# QuadFM.net
KiCad netlist of a schematic drawn in EAGLE
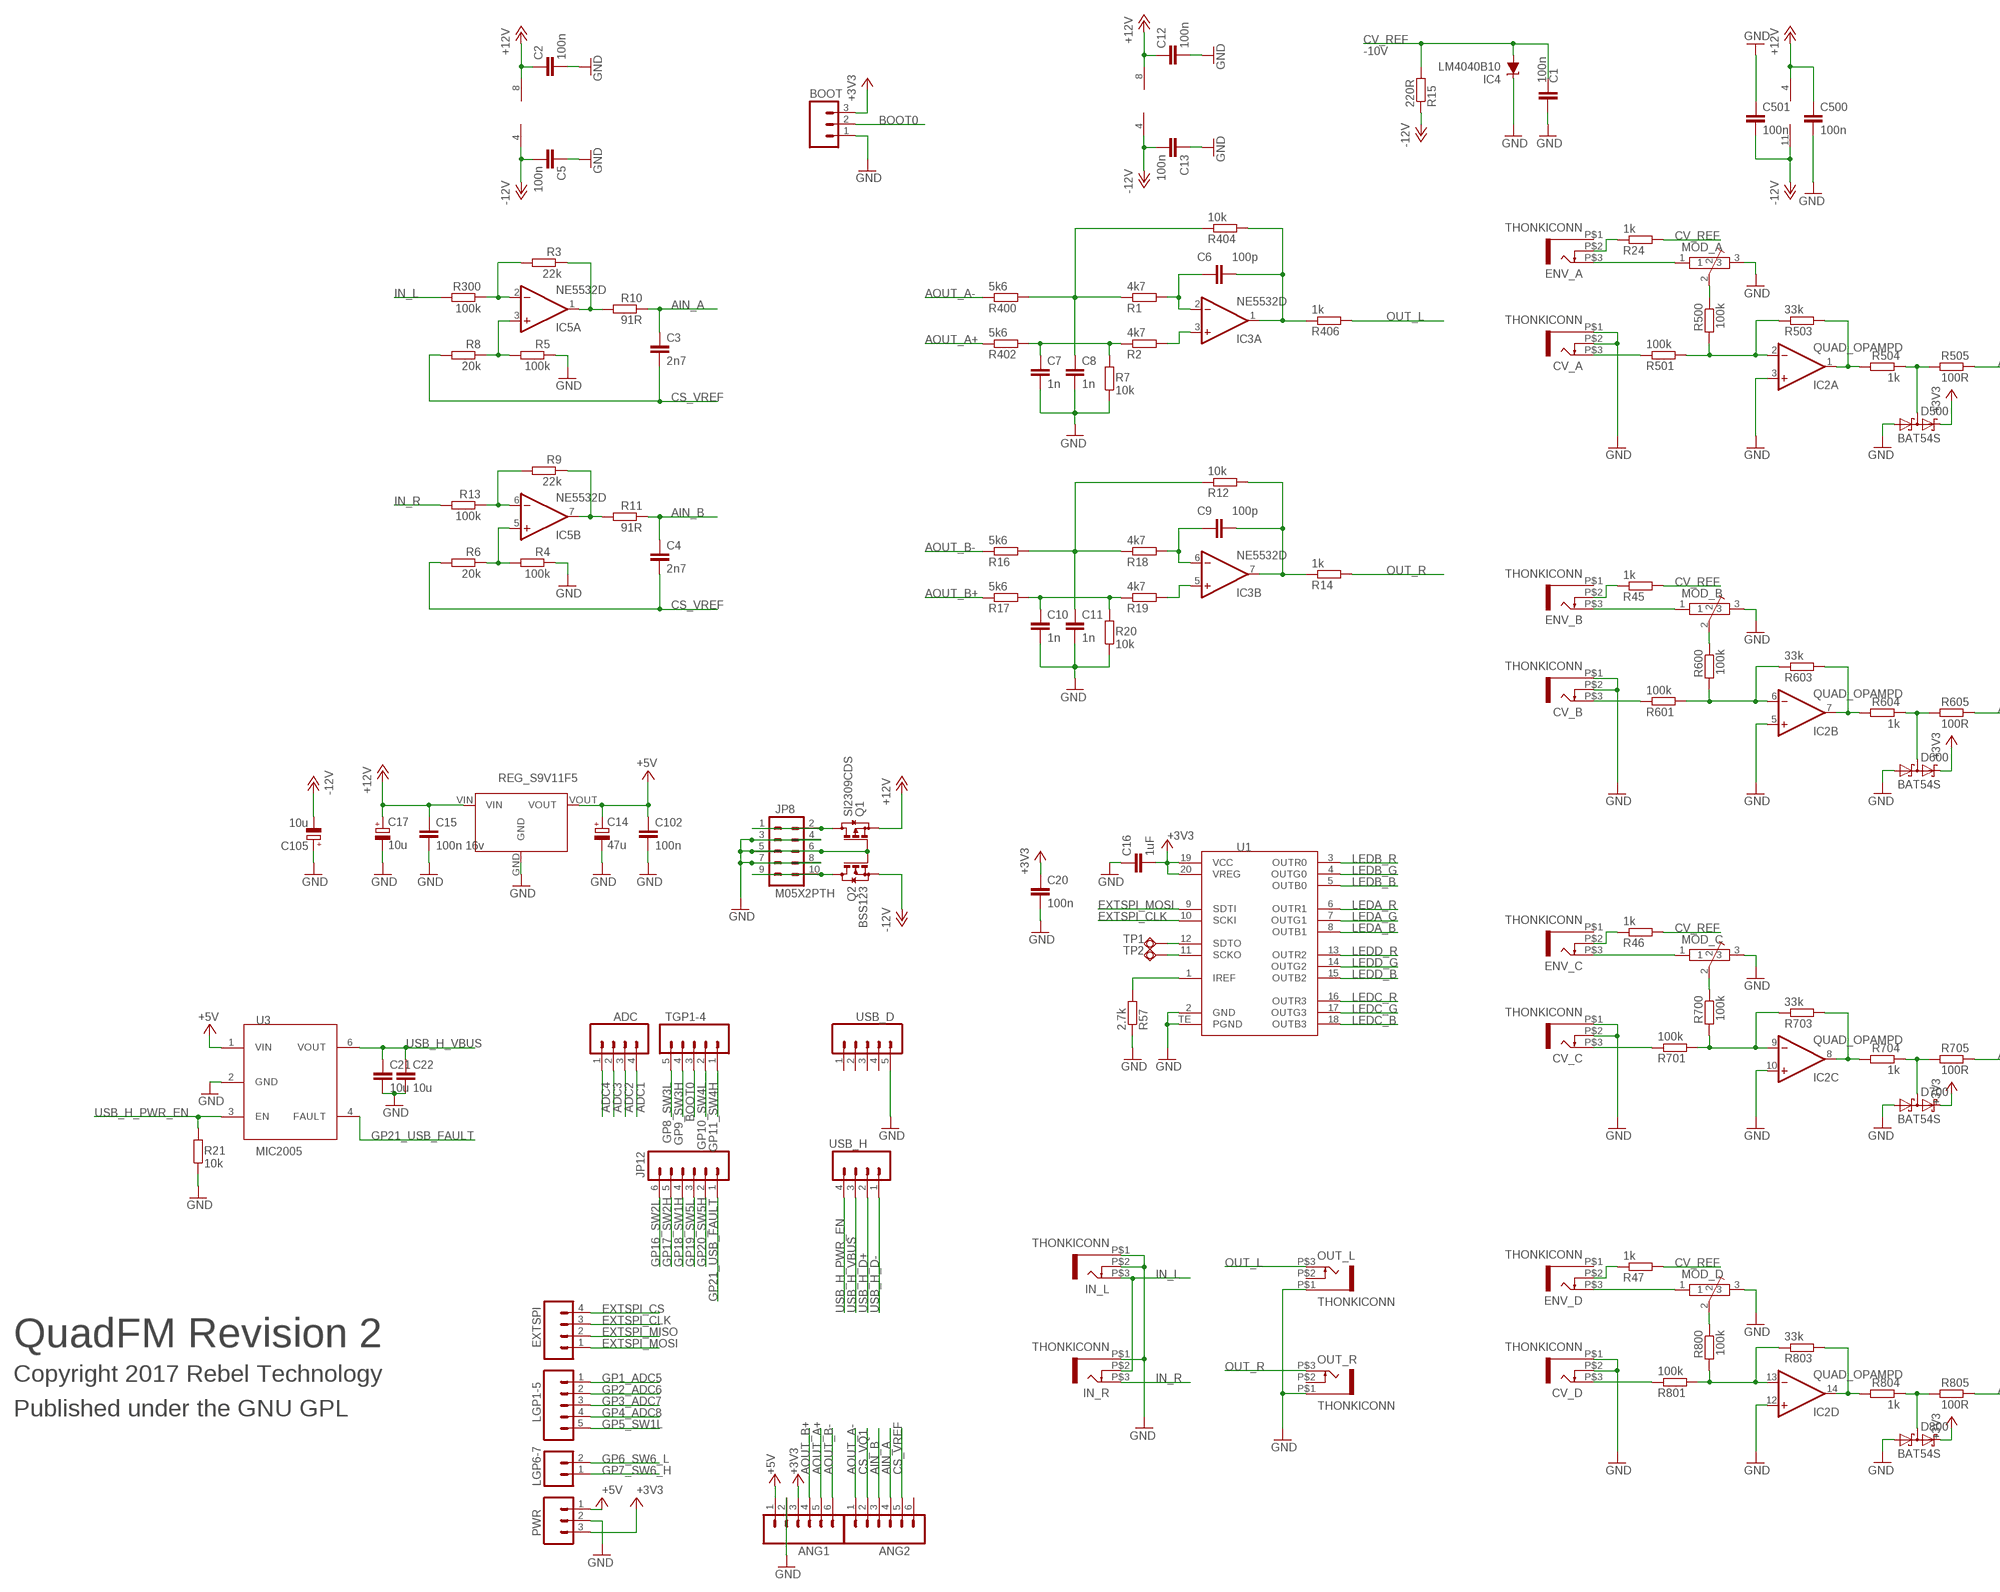
[diagram p0: schematic, sheet 1, part 1 of 2]
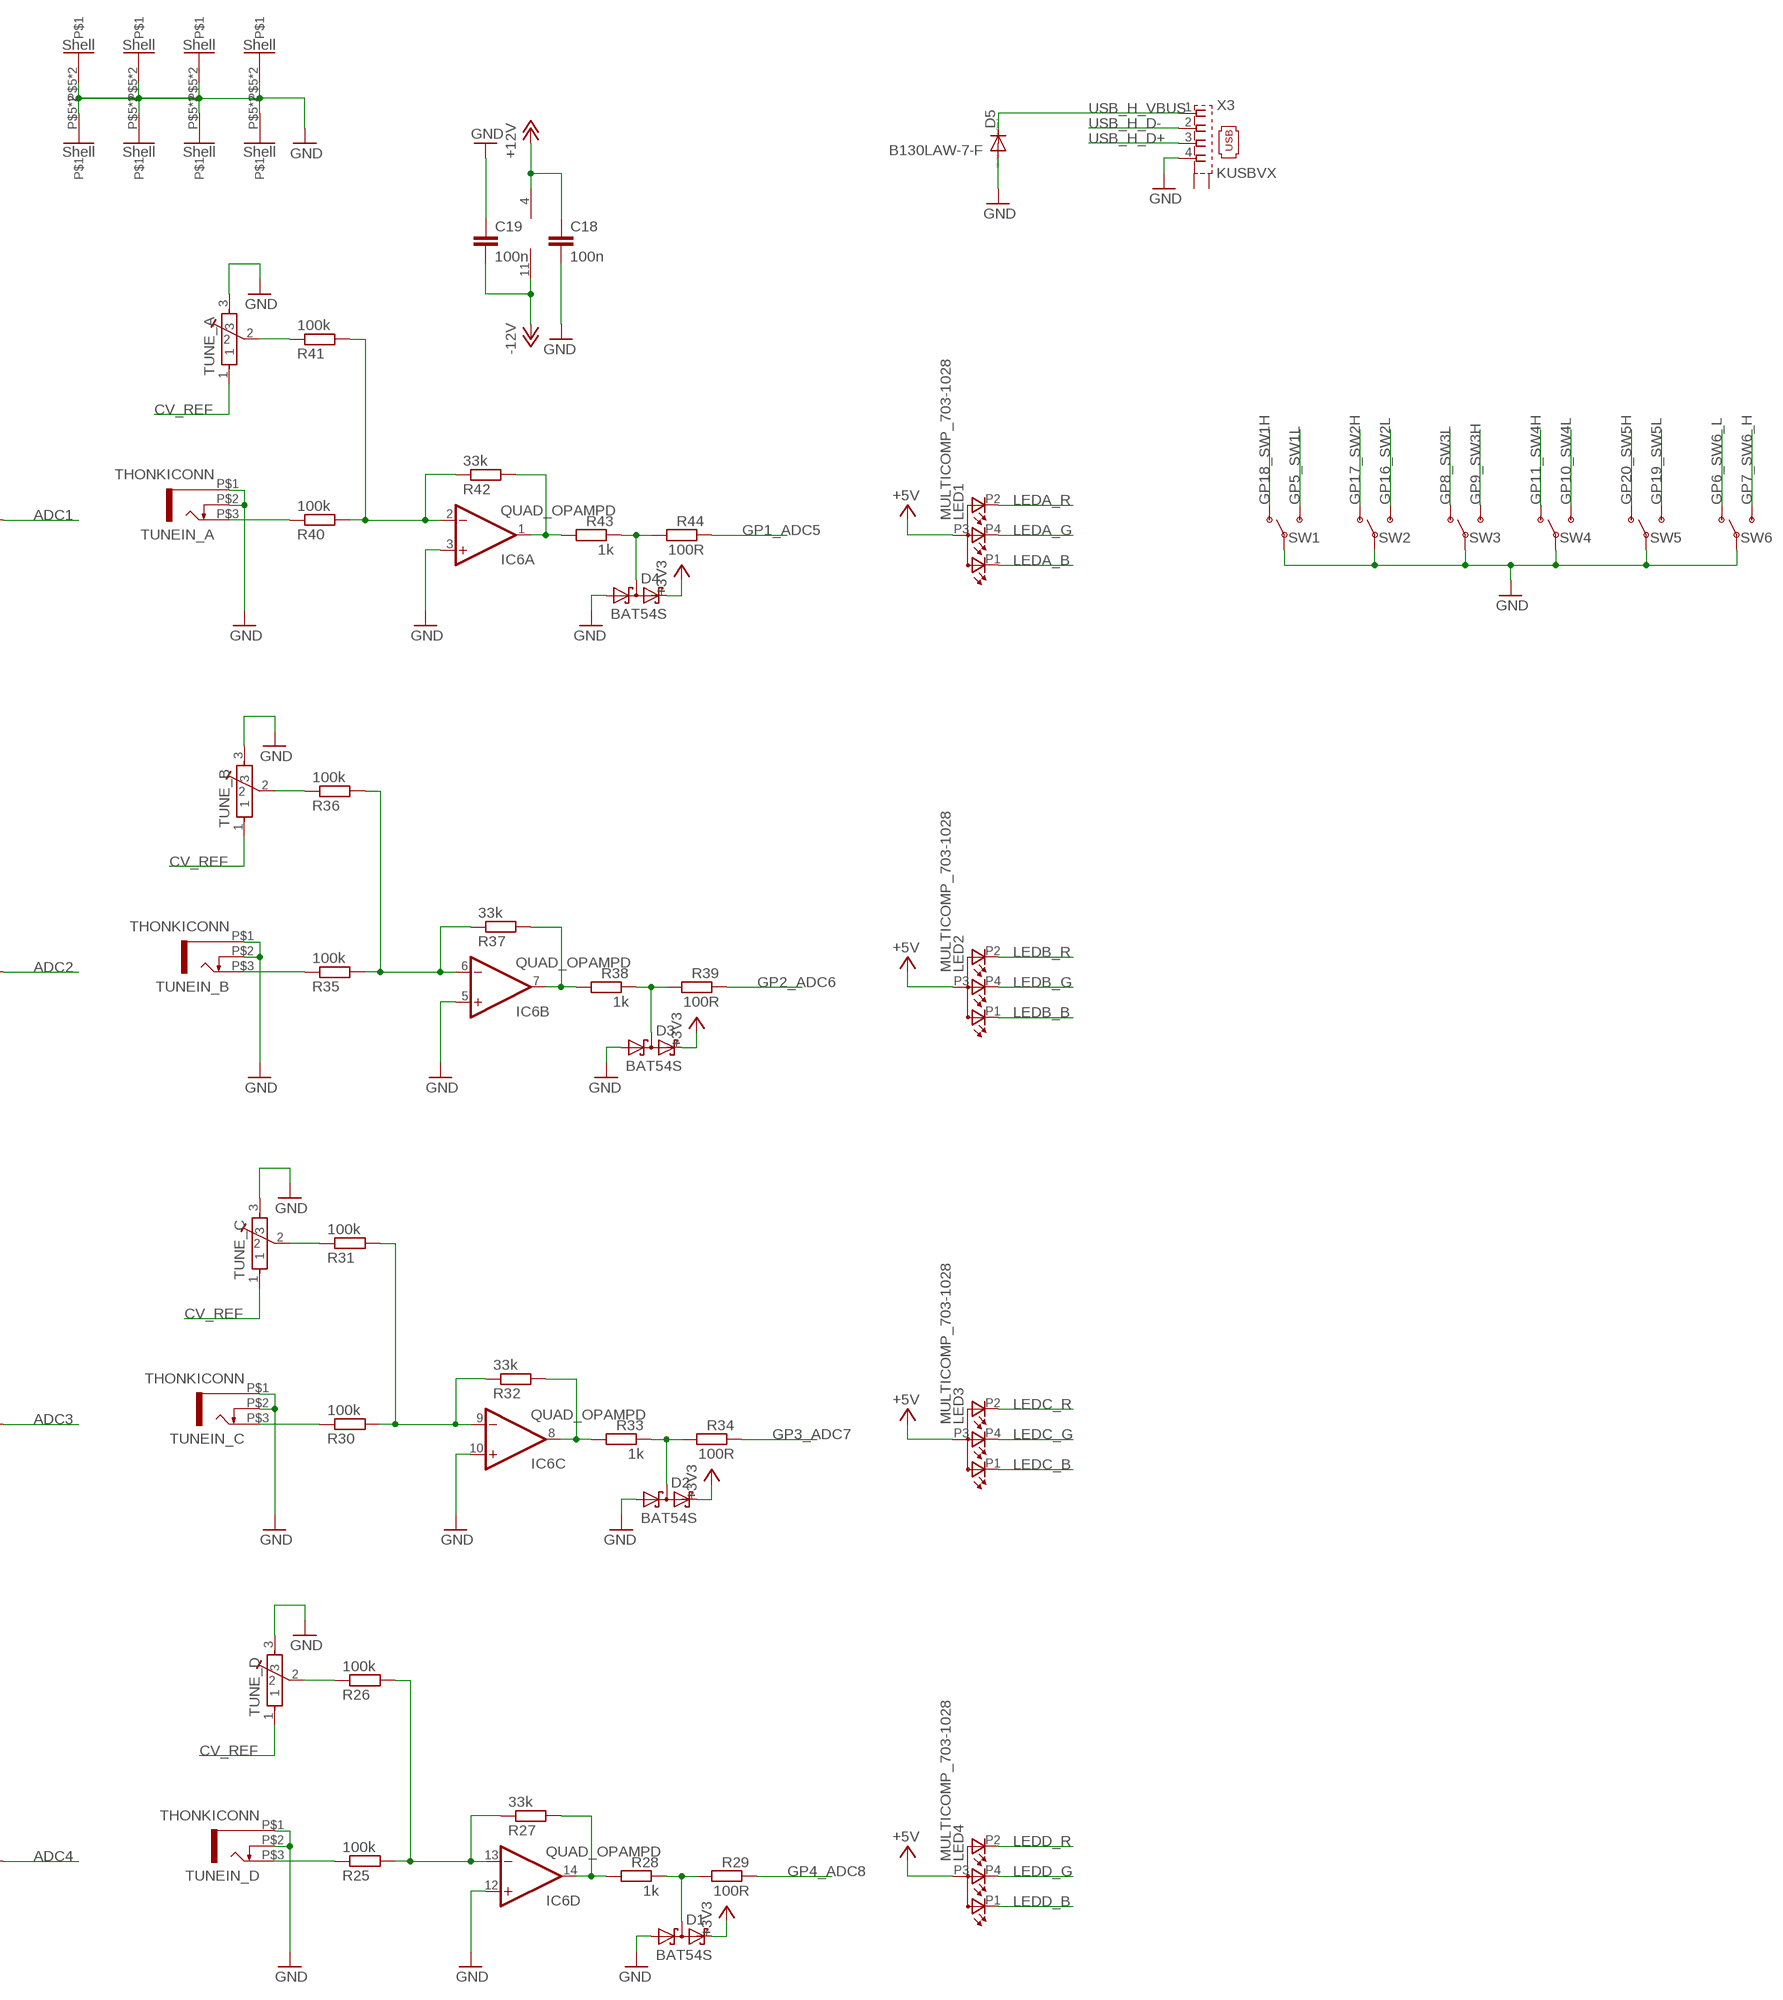
[diagram p1: schematic, sheet 1, part 2 of 2]

(export (version "E")
  (design (tool "Eeschema 10.0.6"))
  (components
    (comp (ref "ADC")
      (value "M04PTH")
      (footprint "eagle-import:1X04")
      (libsource (lib "eagle-import") (part "M04PTH"))
    )
    (comp (ref "ANG1")
      (value "M06SIP")
      (footprint "eagle-import:1X06")
      (libsource (lib "eagle-import") (part "M06SIP"))
    )
    (comp (ref "ANG2")
      (value "M06SIP")
      (footprint "eagle-import:1X06")
      (libsource (lib "eagle-import") (part "M06SIP"))
    )
    (comp (ref "BOOT")
      (value "M03PTH")
      (footprint "eagle-import:1X03")
      (libsource (lib "eagle-import") (part "M03PTH"))
    )
    (comp (ref "C1")
      (value "100n")
      (footprint "eagle-import:C0603")
      (libsource (lib "eagle-import") (part "resistor_C-EUC0603"))
    )
    (comp (ref "C2")
      (value "100n")
      (footprint "eagle-import:C0603")
      (libsource (lib "eagle-import") (part "resistor_C-EUC0603"))
    )
    (comp (ref "C3")
      (value "2n7")
      (footprint "eagle-import:C0603")
      (libsource (lib "eagle-import") (part "resistor_C-EUC0603"))
    )
    (comp (ref "C4")
      (value "2n7")
      (footprint "eagle-import:C0603")
      (libsource (lib "eagle-import") (part "resistor_C-EUC0603"))
    )
    (comp (ref "C5")
      (value "100n")
      (footprint "eagle-import:C0603")
      (libsource (lib "eagle-import") (part "resistor_C-EUC0603"))
    )
    (comp (ref "C6")
      (value "100p")
      (footprint "eagle-import:C0603")
      (libsource (lib "eagle-import") (part "resistor_C-EUC0603"))
    )
    (comp (ref "C7")
      (value "1n")
      (footprint "eagle-import:C0603")
      (libsource (lib "eagle-import") (part "resistor_C-EUC0603"))
    )
    (comp (ref "C8")
      (value "1n")
      (footprint "eagle-import:C0603")
      (libsource (lib "eagle-import") (part "resistor_C-EUC0603"))
    )
    (comp (ref "C9")
      (value "100p")
      (footprint "eagle-import:C0603")
      (libsource (lib "eagle-import") (part "resistor_C-EUC0603"))
    )
    (comp (ref "C10")
      (value "1n")
      (footprint "eagle-import:C0603")
      (libsource (lib "eagle-import") (part "resistor_C-EUC0603"))
    )
    (comp (ref "C11")
      (value "1n")
      (footprint "eagle-import:C0603")
      (libsource (lib "eagle-import") (part "resistor_C-EUC0603"))
    )
    (comp (ref "C12")
      (value "100n")
      (footprint "eagle-import:C0603")
      (libsource (lib "eagle-import") (part "resistor_C-EUC0603"))
    )
    (comp (ref "C13")
      (value "100n")
      (footprint "eagle-import:C0603")
      (libsource (lib "eagle-import") (part "resistor_C-EUC0603"))
    )
    (comp (ref "C14")
      (value "47u")
      (footprint "eagle-import:CPOL-5")
      (libsource (lib "eagle-import") (part "CPOL-EU153CLV-0505"))
    )
    (comp (ref "C15")
      (value "100n 16v")
      (footprint "eagle-import:C0603")
      (libsource (lib "eagle-import") (part "C-EUC0603"))
    )
    (comp (ref "C16")
      (value "1uF")
      (footprint "eagle-import:C0603")
      (libsource (lib "eagle-import") (part "C-EUC0603"))
    )
    (comp (ref "C17")
      (value "10u")
      (footprint "eagle-import:153CLV-0405")
      (libsource (lib "eagle-import") (part "CPOL-EU153CLV-0405"))
    )
    (comp (ref "C18")
      (value "100n")
      (footprint "eagle-import:C0603")
      (libsource (lib "eagle-import") (part "resistor_C-EUC0603"))
    )
    (comp (ref "C19")
      (value "100n")
      (footprint "eagle-import:C0603")
      (libsource (lib "eagle-import") (part "resistor_C-EUC0603"))
    )
    (comp (ref "C20")
      (value "100n")
      (footprint "eagle-import:C0603")
      (libsource (lib "eagle-import") (part "resistor_C-EUC0603"))
    )
    (comp (ref "C21")
      (value "10u")
      (footprint "eagle-import:C0603")
      (libsource (lib "eagle-import") (part "resistor_C-EUC0603"))
    )
    (comp (ref "C22")
      (value "10u")
      (footprint "eagle-import:C0603")
      (libsource (lib "eagle-import") (part "resistor_C-EUC0603"))
    )
    (comp (ref "C102")
      (value "100n")
      (footprint "eagle-import:C0603")
      (libsource (lib "eagle-import") (part "C-EUC0603"))
    )
    (comp (ref "C105")
      (value "10u")
      (footprint "eagle-import:153CLV-0405")
      (libsource (lib "eagle-import") (part "CPOL-EU153CLV-0405"))
    )
    (comp (ref "C500")
      (value "100n")
      (footprint "eagle-import:C0603")
      (libsource (lib "eagle-import") (part "resistor_C-EUC0603"))
    )
    (comp (ref "C501")
      (value "100n")
      (footprint "eagle-import:C0603")
      (libsource (lib "eagle-import") (part "resistor_C-EUC0603"))
    )
    (comp (ref "CV_A")
      (value "THONKICONN")
      (footprint "eagle-import:THONKICONN")
      (libsource (lib "eagle-import") (part "THONKICONN"))
    )
    (comp (ref "CV_B")
      (value "THONKICONN")
      (footprint "eagle-import:THONKICONN")
      (libsource (lib "eagle-import") (part "THONKICONN"))
    )
    (comp (ref "CV_C")
      (value "THONKICONN")
      (footprint "eagle-import:THONKICONN")
      (libsource (lib "eagle-import") (part "THONKICONN"))
    )
    (comp (ref "CV_D")
      (value "THONKICONN")
      (footprint "eagle-import:THONKICONN")
      (libsource (lib "eagle-import") (part "THONKICONN"))
    )
    (comp (ref "D1")
      (value "BAT54S")
      (footprint "eagle-import:SOT23")
      (libsource (lib "eagle-import") (part "BAT54S"))
    )
    (comp (ref "D2")
      (value "BAT54S")
      (footprint "eagle-import:SOT23")
      (libsource (lib "eagle-import") (part "BAT54S"))
    )
    (comp (ref "D3")
      (value "BAT54S")
      (footprint "eagle-import:SOT23")
      (libsource (lib "eagle-import") (part "BAT54S"))
    )
    (comp (ref "D4")
      (value "BAT54S")
      (footprint "eagle-import:SOT23")
      (libsource (lib "eagle-import") (part "BAT54S"))
    )
    (comp (ref "D5")
      (value "B130LAW-7-F")
      (footprint "eagle-import:SOD123")
      (libsource (lib "eagle-import") (part "DIODE-SOD123"))
    )
    (comp (ref "D500")
      (value "BAT54S")
      (footprint "eagle-import:SOT23")
      (libsource (lib "eagle-import") (part "BAT54S"))
    )
    (comp (ref "D600")
      (value "BAT54S")
      (footprint "eagle-import:SOT23")
      (libsource (lib "eagle-import") (part "BAT54S"))
    )
    (comp (ref "D700")
      (value "BAT54S")
      (footprint "eagle-import:SOT23")
      (libsource (lib "eagle-import") (part "BAT54S"))
    )
    (comp (ref "D800")
      (value "BAT54S")
      (footprint "eagle-import:SOT23")
      (libsource (lib "eagle-import") (part "BAT54S"))
    )
    (comp (ref "ENV_A")
      (value "THONKICONN")
      (footprint "eagle-import:THONKICONN")
      (libsource (lib "eagle-import") (part "THONKICONN"))
    )
    (comp (ref "ENV_B")
      (value "THONKICONN")
      (footprint "eagle-import:THONKICONN")
      (libsource (lib "eagle-import") (part "THONKICONN"))
    )
    (comp (ref "ENV_C")
      (value "THONKICONN")
      (footprint "eagle-import:THONKICONN")
      (libsource (lib "eagle-import") (part "THONKICONN"))
    )
    (comp (ref "ENV_D")
      (value "THONKICONN")
      (footprint "eagle-import:THONKICONN")
      (libsource (lib "eagle-import") (part "THONKICONN"))
    )
    (comp (ref "EXTSPI")
      (value "M04PTH")
      (footprint "eagle-import:1X04")
      (libsource (lib "eagle-import") (part "M04PTH"))
    )
    (comp (ref "IC2")
      (value "QUAD_OPAMPD")
      (footprint "eagle-import:SO14")
      (libsource (lib "eagle-import") (part "QUAD_OPAMPD"))
    )
    (comp (ref "IC3")
      (value "NE5532D")
      (footprint "eagle-import:SO08")
      (libsource (lib "eagle-import") (part "NE5532D"))
    )
    (comp (ref "IC4")
      (value "LM4040B10")
      (footprint "eagle-import:DBZ_R-PDSO-G3")
      (fields (field (name "MF") "TEXAS INSTRUMENT CONNECTORS") (field (name "MPN") "LM4041C12QDBZT"))
      (libsource (lib "eagle-import") (part "LM4041DBZC12"))
    )
    (comp (ref "IC5")
      (value "NE5532D")
      (footprint "eagle-import:SO08")
      (libsource (lib "eagle-import") (part "NE5532D"))
    )
    (comp (ref "IC6")
      (value "QUAD_OPAMPD")
      (footprint "eagle-import:SO14")
      (libsource (lib "eagle-import") (part "QUAD_OPAMPD"))
    )
    (comp (ref "IN_L")
      (value "THONKICONN")
      (footprint "eagle-import:THONKICONN")
      (libsource (lib "eagle-import") (part "THONKICONN"))
    )
    (comp (ref "IN_R")
      (value "THONKICONN")
      (footprint "eagle-import:THONKICONN")
      (libsource (lib "eagle-import") (part "THONKICONN"))
    )
    (comp (ref "JP8")
      (value "M05X2PTH")
      (footprint "eagle-import:AVR_ICSP")
      (libsource (lib "eagle-import") (part "M05X2PTH"))
    )
    (comp (ref "JP12")
      (value "M06SIP")
      (footprint "eagle-import:1X06")
      (libsource (lib "eagle-import") (part "M06SIP"))
    )
    (comp (ref "LED1")
      (value "MULTICOMP_703-1028")
      (footprint "eagle-import:RGB-LED-703-1028")
      (libsource (lib "eagle-import") (part "MULTICOMP_703-1028"))
    )
    (comp (ref "LED2")
      (value "MULTICOMP_703-1028")
      (footprint "eagle-import:RGB-LED-703-1028")
      (libsource (lib "eagle-import") (part "MULTICOMP_703-1028"))
    )
    (comp (ref "LED3")
      (value "MULTICOMP_703-1028")
      (footprint "eagle-import:RGB-LED-703-1028")
      (libsource (lib "eagle-import") (part "MULTICOMP_703-1028"))
    )
    (comp (ref "LED4")
      (value "MULTICOMP_703-1028")
      (footprint "eagle-import:RGB-LED-703-1028")
      (libsource (lib "eagle-import") (part "MULTICOMP_703-1028"))
    )
    (comp (ref "LGP1-5")
      (value "M05PTH")
      (footprint "eagle-import:1X05")
      (libsource (lib "eagle-import") (part "M05PTH"))
    )
    (comp (ref "LGP6-7")
      (value "M02PTH")
      (footprint "eagle-import:1X02")
      (libsource (lib "eagle-import") (part "M02PTH"))
    )
    (comp (ref "MOD_A")
      (value "POT-ALPS-RK09L1140")
      (footprint "eagle-import:POT-ALPS-RK09L1140")
      (libsource (lib "eagle-import") (part "POT-ALPS-RK09L1140"))
    )
    (comp (ref "MOD_B")
      (value "POT-ALPS-RK09L1140")
      (footprint "eagle-import:POT-ALPS-RK09L1140")
      (libsource (lib "eagle-import") (part "POT-ALPS-RK09L1140"))
    )
    (comp (ref "MOD_C")
      (value "POT-ALPS-RK09L1140")
      (footprint "eagle-import:POT-ALPS-RK09L1140")
      (libsource (lib "eagle-import") (part "POT-ALPS-RK09L1140"))
    )
    (comp (ref "MOD_D")
      (value "POT-ALPS-RK09L1140")
      (footprint "eagle-import:POT-ALPS-RK09L1140")
      (libsource (lib "eagle-import") (part "POT-ALPS-RK09L1140"))
    )
    (comp (ref "OUT_L")
      (value "THONKICONN")
      (footprint "eagle-import:THONKICONN")
      (libsource (lib "eagle-import") (part "THONKICONN"))
    )
    (comp (ref "OUT_R")
      (value "THONKICONN")
      (footprint "eagle-import:THONKICONN")
      (libsource (lib "eagle-import") (part "THONKICONN"))
    )
    (comp (ref "PWR")
      (value "M03PTH")
      (footprint "eagle-import:1X03")
      (libsource (lib "eagle-import") (part "M03PTH"))
    )
    (comp (ref "Q1")
      (value "SI2309CDS")
      (footprint "eagle-import:SOT23")
      (libsource (lib "eagle-import") (part "BSS84"))
    )
    (comp (ref "Q2")
      (value "BSS123")
      (footprint "eagle-import:SOT23")
      (libsource (lib "eagle-import") (part "BSS123"))
    )
    (comp (ref "R1")
      (value "4k7")
      (footprint "eagle-import:0603")
      (libsource (lib "eagle-import") (part "R-EU_0603"))
    )
    (comp (ref "R2")
      (value "4k7")
      (footprint "eagle-import:0603")
      (libsource (lib "eagle-import") (part "R-EU_0603"))
    )
    (comp (ref "R3")
      (value "22k")
      (footprint "eagle-import:0603")
      (libsource (lib "eagle-import") (part "R-EU_0603"))
    )
    (comp (ref "R4")
      (value "100k")
      (footprint "eagle-import:0603")
      (libsource (lib "eagle-import") (part "R-EU_0603"))
    )
    (comp (ref "R5")
      (value "100k")
      (footprint "eagle-import:0603")
      (libsource (lib "eagle-import") (part "R-EU_0603"))
    )
    (comp (ref "R6")
      (value "20k")
      (footprint "eagle-import:0603")
      (libsource (lib "eagle-import") (part "R-EU_0603"))
    )
    (comp (ref "R7")
      (value "10k")
      (footprint "eagle-import:0603")
      (libsource (lib "eagle-import") (part "R-EU_0603"))
    )
    (comp (ref "R8")
      (value "20k")
      (footprint "eagle-import:0603")
      (libsource (lib "eagle-import") (part "R-EU_0603"))
    )
    (comp (ref "R9")
      (value "22k")
      (footprint "eagle-import:0603")
      (libsource (lib "eagle-import") (part "R-EU_0603"))
    )
    (comp (ref "R10")
      (value "91R")
      (footprint "eagle-import:0603")
      (libsource (lib "eagle-import") (part "R-EU_0603"))
    )
    (comp (ref "R11")
      (value "91R")
      (footprint "eagle-import:0603")
      (libsource (lib "eagle-import") (part "R-EU_0603"))
    )
    (comp (ref "R12")
      (value "10k")
      (footprint "eagle-import:0603")
      (libsource (lib "eagle-import") (part "R-EU_0603"))
    )
    (comp (ref "R13")
      (value "100k")
      (footprint "eagle-import:0603")
      (libsource (lib "eagle-import") (part "R-EU_0603"))
    )
    (comp (ref "R14")
      (value "1k")
      (footprint "eagle-import:0603")
      (libsource (lib "eagle-import") (part "R-EU_0603"))
    )
    (comp (ref "R15")
      (value "220R")
      (footprint "eagle-import:0603")
      (libsource (lib "eagle-import") (part "R-EU_0603"))
    )
    (comp (ref "R16")
      (value "5k6")
      (footprint "eagle-import:0603")
      (libsource (lib "eagle-import") (part "R-EU_0603"))
    )
    (comp (ref "R17")
      (value "5k6")
      (footprint "eagle-import:0603")
      (libsource (lib "eagle-import") (part "R-EU_0603"))
    )
    (comp (ref "R18")
      (value "4k7")
      (footprint "eagle-import:0603")
      (libsource (lib "eagle-import") (part "R-EU_0603"))
    )
    (comp (ref "R19")
      (value "4k7")
      (footprint "eagle-import:0603")
      (libsource (lib "eagle-import") (part "R-EU_0603"))
    )
    (comp (ref "R20")
      (value "10k")
      (footprint "eagle-import:0603")
      (libsource (lib "eagle-import") (part "R-EU_0603"))
    )
    (comp (ref "R21")
      (value "10k")
      (footprint "eagle-import:0603")
      (libsource (lib "eagle-import") (part "R-EU_0603"))
    )
    (comp (ref "R24")
      (value "1k")
      (footprint "eagle-import:0603")
      (libsource (lib "eagle-import") (part "R-EU_0603"))
    )
    (comp (ref "R25")
      (value "100k")
      (footprint "eagle-import:0603")
      (libsource (lib "eagle-import") (part "R-EU_0603"))
    )
    (comp (ref "R26")
      (value "100k")
      (footprint "eagle-import:0603")
      (libsource (lib "eagle-import") (part "R-EU_0603"))
    )
    (comp (ref "R27")
      (value "33k")
      (footprint "eagle-import:0603")
      (libsource (lib "eagle-import") (part "R-EU_0603"))
    )
    (comp (ref "R28")
      (value "1k")
      (footprint "eagle-import:0603")
      (libsource (lib "eagle-import") (part "R-EU_0603"))
    )
    (comp (ref "R29")
      (value "100R")
      (footprint "eagle-import:0603")
      (libsource (lib "eagle-import") (part "R-EU_0603"))
    )
    (comp (ref "R30")
      (value "100k")
      (footprint "eagle-import:0603")
      (libsource (lib "eagle-import") (part "R-EU_0603"))
    )
    (comp (ref "R31")
      (value "100k")
      (footprint "eagle-import:0603")
      (libsource (lib "eagle-import") (part "R-EU_0603"))
    )
    (comp (ref "R32")
      (value "33k")
      (footprint "eagle-import:0603")
      (libsource (lib "eagle-import") (part "R-EU_0603"))
    )
    (comp (ref "R33")
      (value "1k")
      (footprint "eagle-import:0603")
      (libsource (lib "eagle-import") (part "R-EU_0603"))
    )
    (comp (ref "R34")
      (value "100R")
      (footprint "eagle-import:0603")
      (libsource (lib "eagle-import") (part "R-EU_0603"))
    )
    (comp (ref "R35")
      (value "100k")
      (footprint "eagle-import:0603")
      (libsource (lib "eagle-import") (part "R-EU_0603"))
    )
    (comp (ref "R36")
      (value "100k")
      (footprint "eagle-import:0603")
      (libsource (lib "eagle-import") (part "R-EU_0603"))
    )
    (comp (ref "R37")
      (value "33k")
      (footprint "eagle-import:0603")
      (libsource (lib "eagle-import") (part "R-EU_0603"))
    )
    (comp (ref "R38")
      (value "1k")
      (footprint "eagle-import:0603")
      (libsource (lib "eagle-import") (part "R-EU_0603"))
    )
    (comp (ref "R39")
      (value "100R")
      (footprint "eagle-import:0603")
      (libsource (lib "eagle-import") (part "R-EU_0603"))
    )
    (comp (ref "R40")
      (value "100k")
      (footprint "eagle-import:0603")
      (libsource (lib "eagle-import") (part "R-EU_0603"))
    )
    (comp (ref "R41")
      (value "100k")
      (footprint "eagle-import:0603")
      (libsource (lib "eagle-import") (part "R-EU_0603"))
    )
    (comp (ref "R42")
      (value "33k")
      (footprint "eagle-import:0603")
      (libsource (lib "eagle-import") (part "R-EU_0603"))
    )
    (comp (ref "R43")
      (value "1k")
      (footprint "eagle-import:0603")
      (libsource (lib "eagle-import") (part "R-EU_0603"))
    )
    (comp (ref "R44")
      (value "100R")
      (footprint "eagle-import:0603")
      (libsource (lib "eagle-import") (part "R-EU_0603"))
    )
    (comp (ref "R45")
      (value "1k")
      (footprint "eagle-import:0603")
      (libsource (lib "eagle-import") (part "R-EU_0603"))
    )
    (comp (ref "R46")
      (value "1k")
      (footprint "eagle-import:0603")
      (libsource (lib "eagle-import") (part "R-EU_0603"))
    )
    (comp (ref "R47")
      (value "1k")
      (footprint "eagle-import:0603")
      (libsource (lib "eagle-import") (part "R-EU_0603"))
    )
    (comp (ref "R57")
      (value "2.7k")
      (footprint "eagle-import:0603")
      (libsource (lib "eagle-import") (part "R-EU_0603"))
    )
    (comp (ref "R300")
      (value "100k")
      (footprint "eagle-import:0603")
      (libsource (lib "eagle-import") (part "R-EU_0603"))
    )
    (comp (ref "R400")
      (value "5k6")
      (footprint "eagle-import:0603")
      (libsource (lib "eagle-import") (part "R-EU_0603"))
    )
    (comp (ref "R402")
      (value "5k6")
      (footprint "eagle-import:0603")
      (libsource (lib "eagle-import") (part "R-EU_0603"))
    )
    (comp (ref "R404")
      (value "10k")
      (footprint "eagle-import:0603")
      (libsource (lib "eagle-import") (part "R-EU_0603"))
    )
    (comp (ref "R406")
      (value "1k")
      (footprint "eagle-import:0603")
      (libsource (lib "eagle-import") (part "R-EU_0603"))
    )
    (comp (ref "R500")
      (value "100k")
      (footprint "eagle-import:0603")
      (libsource (lib "eagle-import") (part "R-EU_0603"))
    )
    (comp (ref "R501")
      (value "100k")
      (footprint "eagle-import:0603")
      (libsource (lib "eagle-import") (part "R-EU_0603"))
    )
    (comp (ref "R503")
      (value "33k")
      (footprint "eagle-import:0603")
      (libsource (lib "eagle-import") (part "R-EU_0603"))
    )
    (comp (ref "R504")
      (value "1k")
      (footprint "eagle-import:0603")
      (libsource (lib "eagle-import") (part "R-EU_0603"))
    )
    (comp (ref "R505")
      (value "100R")
      (footprint "eagle-import:0603")
      (libsource (lib "eagle-import") (part "R-EU_0603"))
    )
    (comp (ref "R600")
      (value "100k")
      (footprint "eagle-import:0603")
      (libsource (lib "eagle-import") (part "R-EU_0603"))
    )
    (comp (ref "R601")
      (value "100k")
      (footprint "eagle-import:0603")
      (libsource (lib "eagle-import") (part "R-EU_0603"))
    )
    (comp (ref "R603")
      (value "33k")
      (footprint "eagle-import:0603")
      (libsource (lib "eagle-import") (part "R-EU_0603"))
    )
    (comp (ref "R604")
      (value "1k")
      (footprint "eagle-import:0603")
      (libsource (lib "eagle-import") (part "R-EU_0603"))
    )
    (comp (ref "R605")
      (value "100R")
      (footprint "eagle-import:0603")
      (libsource (lib "eagle-import") (part "R-EU_0603"))
    )
    (comp (ref "R700")
      (value "100k")
      (footprint "eagle-import:0603")
      (libsource (lib "eagle-import") (part "R-EU_0603"))
    )
    (comp (ref "R701")
      (value "100k")
      (footprint "eagle-import:0603")
      (libsource (lib "eagle-import") (part "R-EU_0603"))
    )
    (comp (ref "R703")
      (value "33k")
      (footprint "eagle-import:0603")
      (libsource (lib "eagle-import") (part "R-EU_0603"))
    )
    (comp (ref "R704")
      (value "1k")
      (footprint "eagle-import:0603")
      (libsource (lib "eagle-import") (part "R-EU_0603"))
    )
    (comp (ref "R705")
      (value "100R")
      (footprint "eagle-import:0603")
      (libsource (lib "eagle-import") (part "R-EU_0603"))
    )
    (comp (ref "R800")
      (value "100k")
      (footprint "eagle-import:0603")
      (libsource (lib "eagle-import") (part "R-EU_0603"))
    )
    (comp (ref "R801")
      (value "100k")
      (footprint "eagle-import:0603")
      (libsource (lib "eagle-import") (part "R-EU_0603"))
    )
    (comp (ref "R803")
      (value "33k")
      (footprint "eagle-import:0603")
      (libsource (lib "eagle-import") (part "R-EU_0603"))
    )
    (comp (ref "R804")
      (value "1k")
      (footprint "eagle-import:0603")
      (libsource (lib "eagle-import") (part "R-EU_0603"))
    )
    (comp (ref "R805")
      (value "100R")
      (footprint "eagle-import:0603")
      (libsource (lib "eagle-import") (part "R-EU_0603"))
    )
    (comp (ref "SW1")
      (value "SUB-MIN-SPDT")
      (footprint "eagle-import:SUB-MIN-SPDT")
      (libsource (lib "eagle-import") (part "SUB-MIN-SPDT"))
    )
    (comp (ref "SW2")
      (value "SUB-MIN-SPDT")
      (footprint "eagle-import:SUB-MIN-SPDT")
      (libsource (lib "eagle-import") (part "SUB-MIN-SPDT"))
    )
    (comp (ref "SW3")
      (value "SUB-MIN-SPDT")
      (footprint "eagle-import:SUB-MIN-SPDT")
      (libsource (lib "eagle-import") (part "SUB-MIN-SPDT"))
    )
    (comp (ref "SW4")
      (value "SUB-MIN-SPDT")
      (footprint "eagle-import:SUB-MIN-SPDT")
      (libsource (lib "eagle-import") (part "SUB-MIN-SPDT"))
    )
    (comp (ref "SW5")
      (value "SUB-MIN-SPDT")
      (footprint "eagle-import:SUB-MIN-SPDT")
      (libsource (lib "eagle-import") (part "SUB-MIN-SPDT"))
    )
    (comp (ref "SW6")
      (value "SUB-MIN-SPDT")
      (footprint "eagle-import:SUB-MIN-SPDT")
      (libsource (lib "eagle-import") (part "SUB-MIN-SPDT"))
    )
    (comp (ref "TGP1-4")
      (value "M05PTH")
      (footprint "eagle-import:1X05")
      (libsource (lib "eagle-import") (part "M05PTH"))
    )
    (comp (ref "TP1")
      (value "TPSQPAD1-13")
      (footprint "eagle-import:P1-13")
      (libsource (lib "eagle-import") (part "TPSQPAD1-13"))
    )
    (comp (ref "TP2")
      (value "TPSQPAD1-13")
      (footprint "eagle-import:P1-13")
      (libsource (lib "eagle-import") (part "TPSQPAD1-13"))
    )
    (comp (ref "TUNEIN_A")
      (value "THONKICONN")
      (footprint "eagle-import:THONKICONN")
      (libsource (lib "eagle-import") (part "THONKICONN"))
    )
    (comp (ref "TUNEIN_B")
      (value "THONKICONN")
      (footprint "eagle-import:THONKICONN")
      (libsource (lib "eagle-import") (part "THONKICONN"))
    )
    (comp (ref "TUNEIN_C")
      (value "THONKICONN")
      (footprint "eagle-import:THONKICONN")
      (libsource (lib "eagle-import") (part "THONKICONN"))
    )
    (comp (ref "TUNEIN_D")
      (value "THONKICONN")
      (footprint "eagle-import:THONKICONN")
      (libsource (lib "eagle-import") (part "THONKICONN"))
    )
    (comp (ref "TUNE_A")
      (value "POT-ALPS-RK09L1140")
      (footprint "eagle-import:POT-ALPS-RK09L1140")
      (libsource (lib "eagle-import") (part "POT-ALPS-RK09L1140"))
    )
    (comp (ref "TUNE_B")
      (value "POT-ALPS-RK09L1140")
      (footprint "eagle-import:POT-ALPS-RK09L1140")
      (libsource (lib "eagle-import") (part "POT-ALPS-RK09L1140"))
    )
    (comp (ref "TUNE_C")
      (value "POT-ALPS-RK09L1140")
      (footprint "eagle-import:POT-ALPS-RK09L1140")
      (libsource (lib "eagle-import") (part "POT-ALPS-RK09L1140"))
    )
    (comp (ref "TUNE_D")
      (value "POT-ALPS-RK09L1140")
      (footprint "eagle-import:POT-ALPS-RK09L1140")
      (libsource (lib "eagle-import") (part "POT-ALPS-RK09L1140"))
    )
    (comp (ref "U$1")
      (value "REG_S9V11F5")
      (footprint "eagle-import:REG_S9V11F5")
      (libsource (lib "eagle-import") (part "REG_S9V11F5"))
    )
    (comp (ref "U1")
      (value "TLC5971")
      (footprint "eagle-import:TSSOP20-TE")
      (libsource (lib "eagle-import") (part "TLC5971QFN"))
    )
    (comp (ref "U3")
      (value "MIC2005")
      (footprint "eagle-import:SOT23-6")
      (libsource (lib "eagle-import") (part "MIC2005"))
    )
    (comp (ref "USB_D")
      (value "M05PTH")
      (footprint "eagle-import:1X05")
      (libsource (lib "eagle-import") (part "M05PTH"))
    )
    (comp (ref "USB_H")
      (value "M04PTH")
      (footprint "eagle-import:1X04")
      (libsource (lib "eagle-import") (part "M04PTH"))
    )
    (comp (ref "X3")
      (value "KUSBVX")
      (footprint "eagle-import:KUSBVX")
      (libsource (lib "eagle-import") (part "KUSBVX"))
    )
  )
  (nets
    (net (code "1") (name "+3V3") (class "Default")
      (node (ref "ANG1") (pin "3") (pinfunction "3_3") (pintype "passive"))
      (node (ref "BOOT") (pin "3") (pinfunction "3_3") (pintype "passive"))
      (node (ref "C16") (pin "2") (pinfunction "2_2") (pintype "passive"))
      (node (ref "C20") (pin "1") (pinfunction "1_1") (pintype "passive"))
      (node (ref "D1") (pin "2") (pinfunction "C2_2") (pintype "passive"))
      (node (ref "D2") (pin "2") (pinfunction "C2_2") (pintype "passive"))
      (node (ref "D3") (pin "2") (pinfunction "C2_2") (pintype "passive"))
      (node (ref "D4") (pin "2") (pinfunction "C2_2") (pintype "passive"))
      (node (ref "D500") (pin "2") (pinfunction "C2_2") (pintype "passive"))
      (node (ref "D600") (pin "2") (pinfunction "C2_2") (pintype "passive"))
      (node (ref "D700") (pin "2") (pinfunction "C2_2") (pintype "passive"))
      (node (ref "D800") (pin "2") (pinfunction "C2_2") (pintype "passive"))
      (node (ref "PWR") (pin "3") (pinfunction "3_3") (pintype "passive"))
      (node (ref "U1") (pin "19") (pinfunction "VCC_19") (pintype "bidirectional"))
      (node (ref "U1") (pin "20") (pinfunction "VREG_20") (pintype "bidirectional"))
    )
    (net (code "2") (name "+5V") (class "Default")
      (node (ref "ANG1") (pin "1") (pinfunction "1_1") (pintype "passive"))
      (node (ref "C102") (pin "1") (pinfunction "1_1") (pintype "passive"))
      (node (ref "C14") (pin "+") (pinfunction "+_+") (pintype "passive"))
      (node (ref "LED1") (pin "P3") (pinfunction "A_P3") (pintype "passive"))
      (node (ref "LED2") (pin "P3") (pinfunction "A_P3") (pintype "passive"))
      (node (ref "LED3") (pin "P3") (pinfunction "A_P3") (pintype "passive"))
      (node (ref "LED4") (pin "P3") (pinfunction "A_P3") (pintype "passive"))
      (node (ref "PWR") (pin "1") (pinfunction "1_1") (pintype "passive"))
      (node (ref "U$1") (pin "VOUT") (pinfunction "VOUT_VOUT") (pintype "output"))
      (node (ref "U3") (pin "1") (pinfunction "VIN_1") (pintype "power_in"))
    )
    (net (code "3") (name "+12V") (class "Default")
      (node (ref "C12") (pin "1") (pinfunction "1_1") (pintype "passive"))
      (node (ref "C15") (pin "1") (pinfunction "1_1") (pintype "passive"))
      (node (ref "C17") (pin "+") (pinfunction "+_+") (pintype "passive"))
      (node (ref "C18") (pin "1") (pinfunction "1_1") (pintype "passive"))
      (node (ref "C2") (pin "1") (pinfunction "1_1") (pintype "passive"))
      (node (ref "C500") (pin "1") (pinfunction "1_1") (pintype "passive"))
      (node (ref "IC2") (pin "4") (pinfunction "V+_4") (pintype "power_in"))
      (node (ref "IC3") (pin "8") (pinfunction "V+_8") (pintype "power_in"))
      (node (ref "IC5") (pin "8") (pinfunction "V+_8") (pintype "power_in"))
      (node (ref "IC6") (pin "4") (pinfunction "V+_4") (pintype "power_in"))
      (node (ref "Q1") (pin "2") (pinfunction "S_2") (pintype "passive"))
      (node (ref "U$1") (pin "VIN") (pinfunction "VIN_VIN") (pintype "input"))
    )
    (net (code "4") (name "-12V") (class "Default")
      (node (ref "C105") (pin "-") (pinfunction "-_-") (pintype "passive"))
      (node (ref "C13") (pin "2") (pinfunction "2_2") (pintype "passive"))
      (node (ref "C19") (pin "2") (pinfunction "2_2") (pintype "passive"))
      (node (ref "C5") (pin "2") (pinfunction "2_2") (pintype "passive"))
      (node (ref "C501") (pin "2") (pinfunction "2_2") (pintype "passive"))
      (node (ref "IC2") (pin "11") (pinfunction "V-_11") (pintype "power_in"))
      (node (ref "IC3") (pin "4") (pinfunction "V-_4") (pintype "power_in"))
      (node (ref "IC5") (pin "4") (pinfunction "V-_4") (pintype "power_in"))
      (node (ref "IC6") (pin "11") (pinfunction "V-_11") (pintype "power_in"))
      (node (ref "Q2") (pin "2") (pinfunction "S_2") (pintype "passive"))
      (node (ref "R15") (pin "1") (pinfunction "1_1") (pintype "passive"))
    )
    (net (code "5") (name "/ADC1") (class "Default")
      (node (ref "ADC") (pin "4") (pinfunction "4_4") (pintype "passive"))
      (node (ref "R505") (pin "1") (pinfunction "1_1") (pintype "passive"))
    )
    (net (code "6") (name "/ADC2") (class "Default")
      (node (ref "ADC") (pin "3") (pinfunction "3_3") (pintype "passive"))
      (node (ref "R605") (pin "1") (pinfunction "1_1") (pintype "passive"))
    )
    (net (code "7") (name "/ADC3") (class "Default")
      (node (ref "ADC") (pin "2") (pinfunction "2_2") (pintype "passive"))
      (node (ref "R705") (pin "1") (pinfunction "1_1") (pintype "passive"))
    )
    (net (code "8") (name "/ADC4") (class "Default")
      (node (ref "ADC") (pin "1") (pinfunction "1_1") (pintype "passive"))
      (node (ref "R805") (pin "1") (pinfunction "1_1") (pintype "passive"))
    )
    (net (code "9") (name "/AIN_A") (class "Default")
      (node (ref "ANG2") (pin "4") (pinfunction "4_4") (pintype "passive"))
      (node (ref "C3") (pin "1") (pinfunction "1_1") (pintype "passive"))
      (node (ref "R10") (pin "1") (pinfunction "1_1") (pintype "passive"))
    )
    (net (code "10") (name "/AIN_B") (class "Default")
      (node (ref "ANG2") (pin "3") (pinfunction "3_3") (pintype "passive"))
      (node (ref "C4") (pin "1") (pinfunction "1_1") (pintype "passive"))
      (node (ref "R11") (pin "1") (pinfunction "1_1") (pintype "passive"))
    )
    (net (code "11") (name "/AOUT_A+") (class "Default")
      (node (ref "ANG1") (pin "5") (pinfunction "5_5") (pintype "passive"))
      (node (ref "R402") (pin "1") (pinfunction "1_1") (pintype "passive"))
    )
    (net (code "12") (name "/AOUT_A-") (class "Default")
      (node (ref "ANG2") (pin "1") (pinfunction "1_1") (pintype "passive"))
      (node (ref "R400") (pin "1") (pinfunction "1_1") (pintype "passive"))
    )
    (net (code "13") (name "/AOUT_B+") (class "Default")
      (node (ref "ANG1") (pin "4") (pinfunction "4_4") (pintype "passive"))
      (node (ref "R17") (pin "1") (pinfunction "1_1") (pintype "passive"))
    )
    (net (code "14") (name "/AOUT_B-") (class "Default")
      (node (ref "ANG1") (pin "6") (pinfunction "6_6") (pintype "passive"))
      (node (ref "R16") (pin "1") (pinfunction "1_1") (pintype "passive"))
    )
    (net (code "15") (name "/BOOT0") (class "Default")
      (node (ref "BOOT") (pin "2") (pinfunction "2_2") (pintype "passive"))
      (node (ref "TGP1-4") (pin "3") (pinfunction "3_3") (pintype "passive"))
    )
    (net (code "16") (name "/CS_VQ1") (class "Default")
      (node (ref "ANG2") (pin "2") (pinfunction "2_2") (pintype "passive"))
    )
    (net (code "17") (name "/CS_VREF") (class "Default")
      (node (ref "ANG2") (pin "5") (pinfunction "5_5") (pintype "passive"))
      (node (ref "C3") (pin "2") (pinfunction "2_2") (pintype "passive"))
      (node (ref "C4") (pin "2") (pinfunction "2_2") (pintype "passive"))
      (node (ref "R6") (pin "2") (pinfunction "2_2") (pintype "passive"))
      (node (ref "R8") (pin "2") (pinfunction "2_2") (pintype "passive"))
    )
    (net (code "18") (name "/CV_REF") (class "Default")
      (node (ref "C1") (pin "1") (pinfunction "1_1") (pintype "passive"))
      (node (ref "IC4") (pin "2") (pinfunction "A_2") (pintype "passive"))
      (node (ref "R15") (pin "2") (pinfunction "2_2") (pintype "passive"))
      (node (ref "R24") (pin "2") (pinfunction "2_2") (pintype "passive"))
      (node (ref "R45") (pin "2") (pinfunction "2_2") (pintype "passive"))
      (node (ref "R46") (pin "2") (pinfunction "2_2") (pintype "passive"))
      (node (ref "R47") (pin "2") (pinfunction "2_2") (pintype "passive"))
      (node (ref "TUNE_A") (pin "1") (pinfunction "1_1") (pintype "bidirectional"))
      (node (ref "TUNE_B") (pin "1") (pinfunction "1_1") (pintype "bidirectional"))
      (node (ref "TUNE_C") (pin "1") (pinfunction "1_1") (pintype "bidirectional"))
      (node (ref "TUNE_D") (pin "1") (pinfunction "1_1") (pintype "bidirectional"))
    )
    (net (code "19") (name "/EXTSPI_CLK") (class "Default")
      (node (ref "EXTSPI") (pin "3") (pinfunction "3_3") (pintype "passive"))
      (node (ref "U1") (pin "10") (pinfunction "SCKI_10") (pintype "bidirectional"))
    )
    (net (code "20") (name "/EXTSPI_CS") (class "Default")
      (node (ref "EXTSPI") (pin "4") (pinfunction "4_4") (pintype "passive"))
    )
    (net (code "21") (name "/EXTSPI_MISO") (class "Default")
      (node (ref "EXTSPI") (pin "2") (pinfunction "2_2") (pintype "passive"))
    )
    (net (code "22") (name "/EXTSPI_MOSI") (class "Default")
      (node (ref "EXTSPI") (pin "1") (pinfunction "1_1") (pintype "passive"))
      (node (ref "U1") (pin "9") (pinfunction "SDTI_9") (pintype "bidirectional"))
    )
    (net (code "23") (name "/GP1_ADC5") (class "Default")
      (node (ref "LGP1-5") (pin "1") (pinfunction "1_1") (pintype "passive"))
      (node (ref "R44") (pin "1") (pinfunction "1_1") (pintype "passive"))
    )
    (net (code "24") (name "/GP2_ADC6") (class "Default")
      (node (ref "LGP1-5") (pin "2") (pinfunction "2_2") (pintype "passive"))
      (node (ref "R39") (pin "1") (pinfunction "1_1") (pintype "passive"))
    )
    (net (code "25") (name "/GP3_ADC7") (class "Default")
      (node (ref "LGP1-5") (pin "3") (pinfunction "3_3") (pintype "passive"))
      (node (ref "R34") (pin "1") (pinfunction "1_1") (pintype "passive"))
    )
    (net (code "26") (name "/GP4_ADC8") (class "Default")
      (node (ref "LGP1-5") (pin "4") (pinfunction "4_4") (pintype "passive"))
      (node (ref "R29") (pin "1") (pinfunction "1_1") (pintype "passive"))
    )
    (net (code "27") (name "/GP5_SW1L") (class "Default")
      (node (ref "LGP1-5") (pin "5") (pinfunction "5_5") (pintype "passive"))
      (node (ref "SW1") (pin "3") (pinfunction "S_3") (pintype "passive"))
    )
    (net (code "28") (name "/GP6_SW6_L") (class "Default")
      (node (ref "LGP6-7") (pin "2") (pinfunction "2_2") (pintype "passive"))
      (node (ref "SW6") (pin "1") (pinfunction "O_1") (pintype "passive"))
    )
    (net (code "29") (name "/GP7_SW6_H") (class "Default")
      (node (ref "LGP6-7") (pin "1") (pinfunction "1_1") (pintype "passive"))
      (node (ref "SW6") (pin "3") (pinfunction "S_3") (pintype "passive"))
    )
    (net (code "30") (name "/GP8_SW3L") (class "Default")
      (node (ref "SW3") (pin "1") (pinfunction "O_1") (pintype "passive"))
      (node (ref "TGP1-4") (pin "5") (pinfunction "5_5") (pintype "passive"))
    )
    (net (code "31") (name "/GP9_SW3H") (class "Default")
      (node (ref "SW3") (pin "3") (pinfunction "S_3") (pintype "passive"))
      (node (ref "TGP1-4") (pin "4") (pinfunction "4_4") (pintype "passive"))
    )
    (net (code "32") (name "/GP10_SW4L") (class "Default")
      (node (ref "SW4") (pin "3") (pinfunction "S_3") (pintype "passive"))
      (node (ref "TGP1-4") (pin "2") (pinfunction "2_2") (pintype "passive"))
    )
    (net (code "33") (name "/GP11_SW4H") (class "Default")
      (node (ref "SW4") (pin "1") (pinfunction "O_1") (pintype "passive"))
      (node (ref "TGP1-4") (pin "1") (pinfunction "1_1") (pintype "passive"))
    )
    (net (code "34") (name "/GP16_SW2L") (class "Default")
      (node (ref "JP12") (pin "6") (pinfunction "6_6") (pintype "passive"))
      (node (ref "SW2") (pin "3") (pinfunction "S_3") (pintype "passive"))
    )
    (net (code "35") (name "/GP17_SW2H") (class "Default")
      (node (ref "JP12") (pin "5") (pinfunction "5_5") (pintype "passive"))
      (node (ref "SW2") (pin "1") (pinfunction "O_1") (pintype "passive"))
    )
    (net (code "36") (name "/GP18_SW1H") (class "Default")
      (node (ref "JP12") (pin "4") (pinfunction "4_4") (pintype "passive"))
      (node (ref "SW1") (pin "1") (pinfunction "O_1") (pintype "passive"))
    )
    (net (code "37") (name "/GP19_SW5L") (class "Default")
      (node (ref "JP12") (pin "3") (pinfunction "3_3") (pintype "passive"))
      (node (ref "SW5") (pin "3") (pinfunction "S_3") (pintype "passive"))
    )
    (net (code "38") (name "/GP20_SW5H") (class "Default")
      (node (ref "JP12") (pin "2") (pinfunction "2_2") (pintype "passive"))
      (node (ref "SW5") (pin "1") (pinfunction "O_1") (pintype "passive"))
    )
    (net (code "39") (name "/GP21_USB_FAULT") (class "Default")
      (node (ref "JP12") (pin "1") (pinfunction "1_1") (pintype "passive"))
      (node (ref "U3") (pin "4") (pinfunction "FAULT_4") (pintype "output"))
    )
    (net (code "40") (name "/IN_L") (class "Default")
      (node (ref "IN_L") (pin "P$3") (pinfunction "3_P$3") (pintype "passive"))
      (node (ref "IN_R") (pin "P$2") (pinfunction "4_P$2") (pintype "passive"))
      (node (ref "R300") (pin "2") (pinfunction "2_2") (pintype "passive"))
    )
    (net (code "41") (name "/IN_R") (class "Default")
      (node (ref "IN_R") (pin "P$3") (pinfunction "3_P$3") (pintype "passive"))
      (node (ref "R13") (pin "2") (pinfunction "2_2") (pintype "passive"))
    )
    (net (code "42") (name "/LEDA_B") (class "Default")
      (node (ref "LED1") (pin "P1") (pinfunction "CRED_P1") (pintype "passive"))
      (node (ref "U1") (pin "8") (pinfunction "OUTB1_8") (pintype "bidirectional"))
    )
    (net (code "43") (name "/LEDA_G") (class "Default")
      (node (ref "LED1") (pin "P4") (pinfunction "CBLUE_P4") (pintype "passive"))
      (node (ref "U1") (pin "7") (pinfunction "OUTG1_7") (pintype "bidirectional"))
    )
    (net (code "44") (name "/LEDA_R") (class "Default")
      (node (ref "LED1") (pin "P2") (pinfunction "CGREEN_P2") (pintype "passive"))
      (node (ref "U1") (pin "6") (pinfunction "OUTR1_6") (pintype "bidirectional"))
    )
    (net (code "45") (name "/LEDB_B") (class "Default")
      (node (ref "LED2") (pin "P1") (pinfunction "CRED_P1") (pintype "passive"))
      (node (ref "U1") (pin "5") (pinfunction "OUTB0_5") (pintype "bidirectional"))
    )
    (net (code "46") (name "/LEDB_G") (class "Default")
      (node (ref "LED2") (pin "P4") (pinfunction "CBLUE_P4") (pintype "passive"))
      (node (ref "U1") (pin "4") (pinfunction "OUTG0_4") (pintype "bidirectional"))
    )
    (net (code "47") (name "/LEDB_R") (class "Default")
      (node (ref "LED2") (pin "P2") (pinfunction "CGREEN_P2") (pintype "passive"))
      (node (ref "U1") (pin "3") (pinfunction "OUTR0_3") (pintype "bidirectional"))
    )
    (net (code "48") (name "/LEDC_B") (class "Default")
      (node (ref "LED3") (pin "P1") (pinfunction "CRED_P1") (pintype "passive"))
      (node (ref "U1") (pin "18") (pinfunction "OUTB3_18") (pintype "bidirectional"))
    )
    (net (code "49") (name "/LEDC_G") (class "Default")
      (node (ref "LED3") (pin "P4") (pinfunction "CBLUE_P4") (pintype "passive"))
      (node (ref "U1") (pin "17") (pinfunction "OUTG3_17") (pintype "bidirectional"))
    )
    (net (code "50") (name "/LEDC_R") (class "Default")
      (node (ref "LED3") (pin "P2") (pinfunction "CGREEN_P2") (pintype "passive"))
      (node (ref "U1") (pin "16") (pinfunction "OUTR3_16") (pintype "bidirectional"))
    )
    (net (code "51") (name "/LEDD_B") (class "Default")
      (node (ref "LED4") (pin "P1") (pinfunction "CRED_P1") (pintype "passive"))
      (node (ref "U1") (pin "15") (pinfunction "OUTB2_15") (pintype "bidirectional"))
    )
    (net (code "52") (name "/LEDD_G") (class "Default")
      (node (ref "LED4") (pin "P4") (pinfunction "CBLUE_P4") (pintype "passive"))
      (node (ref "U1") (pin "14") (pinfunction "OUTG2_14") (pintype "bidirectional"))
    )
    (net (code "53") (name "/LEDD_R") (class "Default")
      (node (ref "LED4") (pin "P2") (pinfunction "CGREEN_P2") (pintype "passive"))
      (node (ref "U1") (pin "13") (pinfunction "OUTR2_13") (pintype "bidirectional"))
    )
    (net (code "54") (name "/OUT_L") (class "Default")
      (node (ref "OUT_L") (pin "P$3") (pinfunction "3_P$3") (pintype "passive"))
      (node (ref "R406") (pin "2") (pinfunction "2_2") (pintype "passive"))
    )
    (net (code "55") (name "/OUT_R") (class "Default")
      (node (ref "OUT_R") (pin "P$3") (pinfunction "3_P$3") (pintype "passive"))
      (node (ref "R14") (pin "2") (pinfunction "2_2") (pintype "passive"))
    )
    (net (code "56") (name "/USB_H_D+") (class "Default")
      (node (ref "USB_H") (pin "2") (pinfunction "2_2") (pintype "passive"))
      (node (ref "X3") (pin "3") (pinfunction "3_3") (pintype "passive"))
    )
    (net (code "57") (name "/USB_H_D-") (class "Default")
      (node (ref "USB_H") (pin "1") (pinfunction "1_1") (pintype "passive"))
      (node (ref "X3") (pin "2") (pinfunction "2_2") (pintype "passive"))
    )
    (net (code "58") (name "/USB_H_PWR_EN") (class "Default")
      (node (ref "R21") (pin "2") (pinfunction "2_2") (pintype "passive"))
      (node (ref "U3") (pin "3") (pinfunction "EN_3") (pintype "input"))
      (node (ref "USB_H") (pin "4") (pinfunction "4_4") (pintype "passive"))
    )
    (net (code "59") (name "/USB_H_VBUS") (class "Default")
      (node (ref "C21") (pin "1") (pinfunction "1_1") (pintype "passive"))
      (node (ref "C22") (pin "1") (pinfunction "1_1") (pintype "passive"))
      (node (ref "D5") (pin "C") (pinfunction "C_C") (pintype "passive"))
      (node (ref "U3") (pin "6") (pinfunction "VOUT_6") (pintype "output"))
      (node (ref "USB_H") (pin "3") (pinfunction "3_3") (pintype "passive"))
      (node (ref "X3") (pin "1") (pinfunction "1_1") (pintype "passive"))
    )
    (net (code "60") (name "GND") (class "Default")
      (node (ref "ANG1") (pin "2") (pinfunction "2_2") (pintype "passive"))
      (node (ref "BOOT") (pin "1") (pinfunction "1_1") (pintype "passive"))
      (node (ref "C1") (pin "2") (pinfunction "2_2") (pintype "passive"))
      (node (ref "C10") (pin "2") (pinfunction "2_2") (pintype "passive"))
      (node (ref "C102") (pin "2") (pinfunction "2_2") (pintype "passive"))
      (node (ref "C105") (pin "+") (pinfunction "+_+") (pintype "passive"))
      (node (ref "C11") (pin "2") (pinfunction "2_2") (pintype "passive"))
      (node (ref "C12") (pin "2") (pinfunction "2_2") (pintype "passive"))
      (node (ref "C13") (pin "1") (pinfunction "1_1") (pintype "passive"))
      (node (ref "C14") (pin "-") (pinfunction "-_-") (pintype "passive"))
      (node (ref "C15") (pin "2") (pinfunction "2_2") (pintype "passive"))
      (node (ref "C16") (pin "1") (pinfunction "1_1") (pintype "passive"))
      (node (ref "C17") (pin "-") (pinfunction "-_-") (pintype "passive"))
      (node (ref "C18") (pin "2") (pinfunction "2_2") (pintype "passive"))
      (node (ref "C19") (pin "1") (pinfunction "1_1") (pintype "passive"))
      (node (ref "C2") (pin "2") (pinfunction "2_2") (pintype "passive"))
      (node (ref "C20") (pin "2") (pinfunction "2_2") (pintype "passive"))
      (node (ref "C21") (pin "2") (pinfunction "2_2") (pintype "passive"))
      (node (ref "C22") (pin "2") (pinfunction "2_2") (pintype "passive"))
      (node (ref "C5") (pin "1") (pinfunction "1_1") (pintype "passive"))
      (node (ref "C500") (pin "2") (pinfunction "2_2") (pintype "passive"))
      (node (ref "C501") (pin "1") (pinfunction "1_1") (pintype "passive"))
      (node (ref "C7") (pin "2") (pinfunction "2_2") (pintype "passive"))
      (node (ref "C8") (pin "2") (pinfunction "2_2") (pintype "passive"))
      (node (ref "CV_A") (pin "P$1") (pinfunction "5_P$1") (pintype "passive"))
      (node (ref "CV_A") (pin "P$2") (pinfunction "4_P$2") (pintype "passive"))
      (node (ref "CV_B") (pin "P$1") (pinfunction "5_P$1") (pintype "passive"))
      (node (ref "CV_B") (pin "P$2") (pinfunction "4_P$2") (pintype "passive"))
      (node (ref "CV_C") (pin "P$1") (pinfunction "5_P$1") (pintype "passive"))
      (node (ref "CV_C") (pin "P$2") (pinfunction "4_P$2") (pintype "passive"))
      (node (ref "CV_D") (pin "P$1") (pinfunction "5_P$1") (pintype "passive"))
      (node (ref "CV_D") (pin "P$2") (pinfunction "4_P$2") (pintype "passive"))
      (node (ref "D1") (pin "1") (pinfunction "A1_1") (pintype "passive"))
      (node (ref "D2") (pin "1") (pinfunction "A1_1") (pintype "passive"))
      (node (ref "D3") (pin "1") (pinfunction "A1_1") (pintype "passive"))
      (node (ref "D4") (pin "1") (pinfunction "A1_1") (pintype "passive"))
      (node (ref "D5") (pin "A") (pinfunction "A_A") (pintype "passive"))
      (node (ref "D500") (pin "1") (pinfunction "A1_1") (pintype "passive"))
      (node (ref "D600") (pin "1") (pinfunction "A1_1") (pintype "passive"))
      (node (ref "D700") (pin "1") (pinfunction "A1_1") (pintype "passive"))
      (node (ref "D800") (pin "1") (pinfunction "A1_1") (pintype "passive"))
      (node (ref "IC2") (pin "10") (pinfunction "+IN_10") (pintype "input"))
      (node (ref "IC2") (pin "12") (pinfunction "+IN_12") (pintype "input"))
      (node (ref "IC2") (pin "3") (pinfunction "+IN_3") (pintype "input"))
      (node (ref "IC2") (pin "5") (pinfunction "+IN_5") (pintype "input"))
      (node (ref "IC4") (pin "1") (pinfunction "C_1") (pintype "passive"))
      (node (ref "IC6") (pin "10") (pinfunction "+IN_10") (pintype "input"))
      (node (ref "IC6") (pin "12") (pinfunction "+IN_12") (pintype "input"))
      (node (ref "IC6") (pin "3") (pinfunction "+IN_3") (pintype "input"))
      (node (ref "IC6") (pin "5") (pinfunction "+IN_5") (pintype "input"))
      (node (ref "IN_L") (pin "P$1") (pinfunction "5_P$1") (pintype "passive"))
      (node (ref "IN_L") (pin "P$2") (pinfunction "4_P$2") (pintype "passive"))
      (node (ref "IN_R") (pin "P$1") (pinfunction "5_P$1") (pintype "passive"))
      (node (ref "JP8") (pin "3") (pinfunction "3_3") (pintype "passive"))
      (node (ref "JP8") (pin "4") (pinfunction "4_4") (pintype "passive"))
      (node (ref "JP8") (pin "5") (pinfunction "5_5") (pintype "passive"))
      (node (ref "JP8") (pin "6") (pinfunction "6_6") (pintype "passive"))
      (node (ref "JP8") (pin "7") (pinfunction "7_7") (pintype "passive"))
      (node (ref "JP8") (pin "8") (pinfunction "8_8") (pintype "passive"))
      (node (ref "MOD_A") (pin "3") (pinfunction "3_3") (pintype "bidirectional"))
      (node (ref "MOD_A") (pin "P$5") (pinfunction "P$1_P$5") (pintype "bidirectional"))
      (node (ref "MOD_A") (pin "P$6") (pinfunction "P$1_P$6") (pintype "bidirectional"))
      (node (ref "MOD_B") (pin "3") (pinfunction "3_3") (pintype "bidirectional"))
      (node (ref "MOD_B") (pin "P$5") (pinfunction "P$1_P$5") (pintype "bidirectional"))
      (node (ref "MOD_B") (pin "P$6") (pinfunction "P$1_P$6") (pintype "bidirectional"))
      (node (ref "MOD_C") (pin "3") (pinfunction "3_3") (pintype "bidirectional"))
      (node (ref "MOD_C") (pin "P$5") (pinfunction "P$1_P$5") (pintype "bidirectional"))
      (node (ref "MOD_C") (pin "P$6") (pinfunction "P$1_P$6") (pintype "bidirectional"))
      (node (ref "MOD_D") (pin "3") (pinfunction "3_3") (pintype "bidirectional"))
      (node (ref "MOD_D") (pin "P$5") (pinfunction "P$1_P$5") (pintype "bidirectional"))
      (node (ref "MOD_D") (pin "P$6") (pinfunction "P$1_P$6") (pintype "bidirectional"))
      (node (ref "OUT_L") (pin "P$1") (pinfunction "5_P$1") (pintype "passive"))
      (node (ref "OUT_R") (pin "P$1") (pinfunction "5_P$1") (pintype "passive"))
      (node (ref "PWR") (pin "2") (pinfunction "2_2") (pintype "passive"))
      (node (ref "Q1") (pin "1") (pinfunction "G_1") (pintype "passive"))
      (node (ref "Q2") (pin "1") (pinfunction "G_1") (pintype "passive"))
      (node (ref "R20") (pin "1") (pinfunction "1_1") (pintype "passive"))
      (node (ref "R21") (pin "1") (pinfunction "1_1") (pintype "passive"))
      (node (ref "R4") (pin "1") (pinfunction "1_1") (pintype "passive"))
      (node (ref "R5") (pin "1") (pinfunction "1_1") (pintype "passive"))
      (node (ref "R57") (pin "1") (pinfunction "1_1") (pintype "passive"))
      (node (ref "R7") (pin "1") (pinfunction "1_1") (pintype "passive"))
      (node (ref "SW1") (pin "2") (pinfunction "P_2") (pintype "passive"))
      (node (ref "SW2") (pin "2") (pinfunction "P_2") (pintype "passive"))
      (node (ref "SW3") (pin "2") (pinfunction "P_2") (pintype "passive"))
      (node (ref "SW4") (pin "2") (pinfunction "P_2") (pintype "passive"))
      (node (ref "SW5") (pin "2") (pinfunction "P_2") (pintype "passive"))
      (node (ref "SW6") (pin "2") (pinfunction "P_2") (pintype "passive"))
      (node (ref "TUNEIN_A") (pin "P$1") (pinfunction "5_P$1") (pintype "passive"))
      (node (ref "TUNEIN_A") (pin "P$2") (pinfunction "4_P$2") (pintype "passive"))
      (node (ref "TUNEIN_B") (pin "P$1") (pinfunction "5_P$1") (pintype "passive"))
      (node (ref "TUNEIN_B") (pin "P$2") (pinfunction "4_P$2") (pintype "passive"))
      (node (ref "TUNEIN_C") (pin "P$1") (pinfunction "5_P$1") (pintype "passive"))
      (node (ref "TUNEIN_C") (pin "P$2") (pinfunction "4_P$2") (pintype "passive"))
      (node (ref "TUNEIN_D") (pin "P$1") (pinfunction "5_P$1") (pintype "passive"))
      (node (ref "TUNEIN_D") (pin "P$2") (pinfunction "4_P$2") (pintype "passive"))
      (node (ref "TUNE_A") (pin "3") (pinfunction "3_3") (pintype "bidirectional"))
      (node (ref "TUNE_A") (pin "P$5") (pinfunction "P$1_P$5") (pintype "bidirectional"))
      (node (ref "TUNE_A") (pin "P$6") (pinfunction "P$1_P$6") (pintype "bidirectional"))
      (node (ref "TUNE_B") (pin "3") (pinfunction "3_3") (pintype "bidirectional"))
      (node (ref "TUNE_B") (pin "P$5") (pinfunction "P$1_P$5") (pintype "bidirectional"))
      (node (ref "TUNE_B") (pin "P$6") (pinfunction "P$1_P$6") (pintype "bidirectional"))
      (node (ref "TUNE_C") (pin "3") (pinfunction "3_3") (pintype "bidirectional"))
      (node (ref "TUNE_C") (pin "P$5") (pinfunction "P$1_P$5") (pintype "bidirectional"))
      (node (ref "TUNE_C") (pin "P$6") (pinfunction "P$1_P$6") (pintype "bidirectional"))
      (node (ref "TUNE_D") (pin "3") (pinfunction "3_3") (pintype "bidirectional"))
      (node (ref "TUNE_D") (pin "P$5") (pinfunction "P$1_P$5") (pintype "bidirectional"))
      (node (ref "TUNE_D") (pin "P$6") (pinfunction "P$1_P$6") (pintype "bidirectional"))
      (node (ref "U$1") (pin "GND") (pinfunction "GND_GND") (pintype "power_in"))
      (node (ref "U1") (pin "2") (pinfunction "GND_2") (pintype "bidirectional"))
      (node (ref "U1") (pin "TE") (pinfunction "PGND_TE") (pintype "bidirectional"))
      (node (ref "U3") (pin "2") (pinfunction "GND_2") (pintype "power_in"))
      (node (ref "USB_D") (pin "5") (pinfunction "5_5") (pintype "passive"))
      (node (ref "X3") (pin "4") (pinfunction "4_4") (pintype "passive"))
    )
    (net (code "61") (name "Net-(C7-Pad1)") (class "Default")
      (node (ref "C7") (pin "1") (pinfunction "1_1") (pintype "passive"))
      (node (ref "R2") (pin "1") (pinfunction "1_1") (pintype "passive"))
      (node (ref "R402") (pin "2") (pinfunction "2_2") (pintype "passive"))
      (node (ref "R7") (pin "2") (pinfunction "2_2") (pintype "passive"))
    )
    (net (code "62") (name "Net-(C8-Pad1)") (class "Default")
      (node (ref "C8") (pin "1") (pinfunction "1_1") (pintype "passive"))
      (node (ref "R1") (pin "1") (pinfunction "1_1") (pintype "passive"))
      (node (ref "R400") (pin "2") (pinfunction "2_2") (pintype "passive"))
      (node (ref "R404") (pin "1") (pinfunction "1_1") (pintype "passive"))
    )
    (net (code "63") (name "Net-(C10-Pad1)") (class "Default")
      (node (ref "C10") (pin "1") (pinfunction "1_1") (pintype "passive"))
      (node (ref "R17") (pin "2") (pinfunction "2_2") (pintype "passive"))
      (node (ref "R19") (pin "1") (pinfunction "1_1") (pintype "passive"))
      (node (ref "R20") (pin "2") (pinfunction "2_2") (pintype "passive"))
    )
    (net (code "64") (name "Net-(C11-Pad1)") (class "Default")
      (node (ref "C11") (pin "1") (pinfunction "1_1") (pintype "passive"))
      (node (ref "R12") (pin "1") (pinfunction "1_1") (pintype "passive"))
      (node (ref "R16") (pin "2") (pinfunction "2_2") (pintype "passive"))
      (node (ref "R18") (pin "1") (pinfunction "1_1") (pintype "passive"))
    )
    (net (code "65") (name "Net-(CV_A-3)") (class "Default")
      (node (ref "CV_A") (pin "P$3") (pinfunction "3_P$3") (pintype "passive"))
      (node (ref "R501") (pin "1") (pinfunction "1_1") (pintype "passive"))
    )
    (net (code "66") (name "Net-(CV_B-3)") (class "Default")
      (node (ref "CV_B") (pin "P$3") (pinfunction "3_P$3") (pintype "passive"))
      (node (ref "R601") (pin "1") (pinfunction "1_1") (pintype "passive"))
    )
    (net (code "67") (name "Net-(CV_C-3)") (class "Default")
      (node (ref "CV_C") (pin "P$3") (pinfunction "3_P$3") (pintype "passive"))
      (node (ref "R701") (pin "1") (pinfunction "1_1") (pintype "passive"))
    )
    (net (code "68") (name "Net-(CV_D-3)") (class "Default")
      (node (ref "CV_D") (pin "P$3") (pinfunction "3_P$3") (pintype "passive"))
      (node (ref "R801") (pin "1") (pinfunction "1_1") (pintype "passive"))
    )
    (net (code "69") (name "Net-(D1-C1A2)") (class "Default")
      (node (ref "D1") (pin "3") (pinfunction "C1A2_3") (pintype "passive"))
      (node (ref "R28") (pin "1") (pinfunction "1_1") (pintype "passive"))
      (node (ref "R29") (pin "2") (pinfunction "2_2") (pintype "passive"))
    )
    (net (code "70") (name "Net-(D2-C1A2)") (class "Default")
      (node (ref "D2") (pin "3") (pinfunction "C1A2_3") (pintype "passive"))
      (node (ref "R33") (pin "1") (pinfunction "1_1") (pintype "passive"))
      (node (ref "R34") (pin "2") (pinfunction "2_2") (pintype "passive"))
    )
    (net (code "71") (name "Net-(D3-C1A2)") (class "Default")
      (node (ref "D3") (pin "3") (pinfunction "C1A2_3") (pintype "passive"))
      (node (ref "R38") (pin "1") (pinfunction "1_1") (pintype "passive"))
      (node (ref "R39") (pin "2") (pinfunction "2_2") (pintype "passive"))
    )
    (net (code "72") (name "Net-(D4-C1A2)") (class "Default")
      (node (ref "D4") (pin "3") (pinfunction "C1A2_3") (pintype "passive"))
      (node (ref "R43") (pin "1") (pinfunction "1_1") (pintype "passive"))
      (node (ref "R44") (pin "2") (pinfunction "2_2") (pintype "passive"))
    )
    (net (code "73") (name "Net-(D500-C1A2)") (class "Default")
      (node (ref "D500") (pin "3") (pinfunction "C1A2_3") (pintype "passive"))
      (node (ref "R504") (pin "1") (pinfunction "1_1") (pintype "passive"))
      (node (ref "R505") (pin "2") (pinfunction "2_2") (pintype "passive"))
    )
    (net (code "74") (name "Net-(D600-C1A2)") (class "Default")
      (node (ref "D600") (pin "3") (pinfunction "C1A2_3") (pintype "passive"))
      (node (ref "R604") (pin "1") (pinfunction "1_1") (pintype "passive"))
      (node (ref "R605") (pin "2") (pinfunction "2_2") (pintype "passive"))
    )
    (net (code "75") (name "Net-(D700-C1A2)") (class "Default")
      (node (ref "D700") (pin "3") (pinfunction "C1A2_3") (pintype "passive"))
      (node (ref "R704") (pin "1") (pinfunction "1_1") (pintype "passive"))
      (node (ref "R705") (pin "2") (pinfunction "2_2") (pintype "passive"))
    )
    (net (code "76") (name "Net-(D800-C1A2)") (class "Default")
      (node (ref "D800") (pin "3") (pinfunction "C1A2_3") (pintype "passive"))
      (node (ref "R804") (pin "1") (pinfunction "1_1") (pintype "passive"))
      (node (ref "R805") (pin "2") (pinfunction "2_2") (pintype "passive"))
    )
    (net (code "77") (name "Net-(ENV_A-3)") (class "Default")
      (node (ref "ENV_A") (pin "P$3") (pinfunction "3_P$3") (pintype "passive"))
      (node (ref "MOD_A") (pin "1") (pinfunction "1_1") (pintype "bidirectional"))
    )
    (net (code "78") (name "Net-(ENV_A-4)") (class "Default")
      (node (ref "ENV_A") (pin "P$2") (pinfunction "4_P$2") (pintype "passive"))
      (node (ref "R24") (pin "1") (pinfunction "1_1") (pintype "passive"))
    )
    (net (code "79") (name "Net-(ENV_B-3)") (class "Default")
      (node (ref "ENV_B") (pin "P$3") (pinfunction "3_P$3") (pintype "passive"))
      (node (ref "MOD_B") (pin "1") (pinfunction "1_1") (pintype "bidirectional"))
    )
    (net (code "80") (name "Net-(ENV_B-4)") (class "Default")
      (node (ref "ENV_B") (pin "P$2") (pinfunction "4_P$2") (pintype "passive"))
      (node (ref "R45") (pin "1") (pinfunction "1_1") (pintype "passive"))
    )
    (net (code "81") (name "Net-(ENV_C-3)") (class "Default")
      (node (ref "ENV_C") (pin "P$3") (pinfunction "3_P$3") (pintype "passive"))
      (node (ref "MOD_C") (pin "1") (pinfunction "1_1") (pintype "bidirectional"))
    )
    (net (code "82") (name "Net-(ENV_C-4)") (class "Default")
      (node (ref "ENV_C") (pin "P$2") (pinfunction "4_P$2") (pintype "passive"))
      (node (ref "R46") (pin "1") (pinfunction "1_1") (pintype "passive"))
    )
    (net (code "83") (name "Net-(ENV_D-3)") (class "Default")
      (node (ref "ENV_D") (pin "P$3") (pinfunction "3_P$3") (pintype "passive"))
      (node (ref "MOD_D") (pin "1") (pinfunction "1_1") (pintype "bidirectional"))
    )
    (net (code "84") (name "Net-(ENV_D-4)") (class "Default")
      (node (ref "ENV_D") (pin "P$2") (pinfunction "4_P$2") (pintype "passive"))
      (node (ref "R47") (pin "1") (pinfunction "1_1") (pintype "passive"))
    )
    (net (code "85") (name "Net-(IC2A--IN)") (class "Default")
      (node (ref "IC2") (pin "2") (pinfunction "-IN_2") (pintype "input"))
      (node (ref "R500") (pin "2") (pinfunction "2_2") (pintype "passive"))
      (node (ref "R501") (pin "2") (pinfunction "2_2") (pintype "passive"))
      (node (ref "R503") (pin "1") (pinfunction "1_1") (pintype "passive"))
    )
    (net (code "86") (name "Net-(IC2A-OUT)") (class "Default")
      (node (ref "IC2") (pin "1") (pinfunction "OUT_1") (pintype "output"))
      (node (ref "R503") (pin "2") (pinfunction "2_2") (pintype "passive"))
      (node (ref "R504") (pin "2") (pinfunction "2_2") (pintype "passive"))
    )
    (net (code "87") (name "Net-(IC2B--IN)") (class "Default")
      (node (ref "IC2") (pin "6") (pinfunction "-IN_6") (pintype "input"))
      (node (ref "R600") (pin "2") (pinfunction "2_2") (pintype "passive"))
      (node (ref "R601") (pin "2") (pinfunction "2_2") (pintype "passive"))
      (node (ref "R603") (pin "1") (pinfunction "1_1") (pintype "passive"))
    )
    (net (code "88") (name "Net-(IC2B-OUT)") (class "Default")
      (node (ref "IC2") (pin "7") (pinfunction "OUT_7") (pintype "output"))
      (node (ref "R603") (pin "2") (pinfunction "2_2") (pintype "passive"))
      (node (ref "R604") (pin "2") (pinfunction "2_2") (pintype "passive"))
    )
    (net (code "89") (name "Net-(IC2C--IN)") (class "Default")
      (node (ref "IC2") (pin "9") (pinfunction "-IN_9") (pintype "input"))
      (node (ref "R700") (pin "2") (pinfunction "2_2") (pintype "passive"))
      (node (ref "R701") (pin "2") (pinfunction "2_2") (pintype "passive"))
      (node (ref "R703") (pin "1") (pinfunction "1_1") (pintype "passive"))
    )
    (net (code "90") (name "Net-(IC2C-OUT)") (class "Default")
      (node (ref "IC2") (pin "8") (pinfunction "OUT_8") (pintype "output"))
      (node (ref "R703") (pin "2") (pinfunction "2_2") (pintype "passive"))
      (node (ref "R704") (pin "2") (pinfunction "2_2") (pintype "passive"))
    )
    (net (code "91") (name "Net-(IC2D--IN)") (class "Default")
      (node (ref "IC2") (pin "13") (pinfunction "-IN_13") (pintype "input"))
      (node (ref "R800") (pin "2") (pinfunction "2_2") (pintype "passive"))
      (node (ref "R801") (pin "2") (pinfunction "2_2") (pintype "passive"))
      (node (ref "R803") (pin "1") (pinfunction "1_1") (pintype "passive"))
    )
    (net (code "92") (name "Net-(IC2D-OUT)") (class "Default")
      (node (ref "IC2") (pin "14") (pinfunction "OUT_14") (pintype "output"))
      (node (ref "R803") (pin "2") (pinfunction "2_2") (pintype "passive"))
      (node (ref "R804") (pin "2") (pinfunction "2_2") (pintype "passive"))
    )
    (net (code "93") (name "Net-(IC3A-+IN)") (class "Default")
      (node (ref "IC3") (pin "3") (pinfunction "+IN_3") (pintype "input"))
      (node (ref "R2") (pin "2") (pinfunction "2_2") (pintype "passive"))
    )
    (net (code "94") (name "Net-(IC3A--IN)") (class "Default")
      (node (ref "C6") (pin "1") (pinfunction "1_1") (pintype "passive"))
      (node (ref "IC3") (pin "2") (pinfunction "-IN_2") (pintype "input"))
      (node (ref "R1") (pin "2") (pinfunction "2_2") (pintype "passive"))
    )
    (net (code "95") (name "Net-(IC3A-OUT)") (class "Default")
      (node (ref "C6") (pin "2") (pinfunction "2_2") (pintype "passive"))
      (node (ref "IC3") (pin "1") (pinfunction "OUT_1") (pintype "output"))
      (node (ref "R404") (pin "2") (pinfunction "2_2") (pintype "passive"))
      (node (ref "R406") (pin "1") (pinfunction "1_1") (pintype "passive"))
    )
    (net (code "96") (name "Net-(IC3B-+IN)") (class "Default")
      (node (ref "IC3") (pin "5") (pinfunction "+IN_5") (pintype "input"))
      (node (ref "R19") (pin "2") (pinfunction "2_2") (pintype "passive"))
    )
    (net (code "97") (name "Net-(IC3B--IN)") (class "Default")
      (node (ref "C9") (pin "1") (pinfunction "1_1") (pintype "passive"))
      (node (ref "IC3") (pin "6") (pinfunction "-IN_6") (pintype "input"))
      (node (ref "R18") (pin "2") (pinfunction "2_2") (pintype "passive"))
    )
    (net (code "98") (name "Net-(IC3B-OUT)") (class "Default")
      (node (ref "C9") (pin "2") (pinfunction "2_2") (pintype "passive"))
      (node (ref "IC3") (pin "7") (pinfunction "OUT_7") (pintype "output"))
      (node (ref "R12") (pin "2") (pinfunction "2_2") (pintype "passive"))
      (node (ref "R14") (pin "1") (pinfunction "1_1") (pintype "passive"))
    )
    (net (code "99") (name "Net-(IC5A-+IN)") (class "Default")
      (node (ref "IC5") (pin "3") (pinfunction "+IN_3") (pintype "input"))
      (node (ref "R5") (pin "2") (pinfunction "2_2") (pintype "passive"))
      (node (ref "R8") (pin "1") (pinfunction "1_1") (pintype "passive"))
    )
    (net (code "100") (name "Net-(IC5A--IN)") (class "Default")
      (node (ref "IC5") (pin "2") (pinfunction "-IN_2") (pintype "input"))
      (node (ref "R3") (pin "2") (pinfunction "2_2") (pintype "passive"))
      (node (ref "R300") (pin "1") (pinfunction "1_1") (pintype "passive"))
    )
    (net (code "101") (name "Net-(IC5A-OUT)") (class "Default")
      (node (ref "IC5") (pin "1") (pinfunction "OUT_1") (pintype "output"))
      (node (ref "R10") (pin "2") (pinfunction "2_2") (pintype "passive"))
      (node (ref "R3") (pin "1") (pinfunction "1_1") (pintype "passive"))
    )
    (net (code "102") (name "Net-(IC5B-+IN)") (class "Default")
      (node (ref "IC5") (pin "5") (pinfunction "+IN_5") (pintype "input"))
      (node (ref "R4") (pin "2") (pinfunction "2_2") (pintype "passive"))
      (node (ref "R6") (pin "1") (pinfunction "1_1") (pintype "passive"))
    )
    (net (code "103") (name "Net-(IC5B--IN)") (class "Default")
      (node (ref "IC5") (pin "6") (pinfunction "-IN_6") (pintype "input"))
      (node (ref "R13") (pin "1") (pinfunction "1_1") (pintype "passive"))
      (node (ref "R9") (pin "2") (pinfunction "2_2") (pintype "passive"))
    )
    (net (code "104") (name "Net-(IC5B-OUT)") (class "Default")
      (node (ref "IC5") (pin "7") (pinfunction "OUT_7") (pintype "output"))
      (node (ref "R11") (pin "2") (pinfunction "2_2") (pintype "passive"))
      (node (ref "R9") (pin "1") (pinfunction "1_1") (pintype "passive"))
    )
    (net (code "105") (name "Net-(IC6A--IN)") (class "Default")
      (node (ref "IC6") (pin "2") (pinfunction "-IN_2") (pintype "input"))
      (node (ref "R40") (pin "2") (pinfunction "2_2") (pintype "passive"))
      (node (ref "R41") (pin "2") (pinfunction "2_2") (pintype "passive"))
      (node (ref "R42") (pin "1") (pinfunction "1_1") (pintype "passive"))
    )
    (net (code "106") (name "Net-(IC6A-OUT)") (class "Default")
      (node (ref "IC6") (pin "1") (pinfunction "OUT_1") (pintype "output"))
      (node (ref "R42") (pin "2") (pinfunction "2_2") (pintype "passive"))
      (node (ref "R43") (pin "2") (pinfunction "2_2") (pintype "passive"))
    )
    (net (code "107") (name "Net-(IC6B--IN)") (class "Default")
      (node (ref "IC6") (pin "6") (pinfunction "-IN_6") (pintype "input"))
      (node (ref "R35") (pin "2") (pinfunction "2_2") (pintype "passive"))
      (node (ref "R36") (pin "2") (pinfunction "2_2") (pintype "passive"))
      (node (ref "R37") (pin "1") (pinfunction "1_1") (pintype "passive"))
    )
    (net (code "108") (name "Net-(IC6B-OUT)") (class "Default")
      (node (ref "IC6") (pin "7") (pinfunction "OUT_7") (pintype "output"))
      (node (ref "R37") (pin "2") (pinfunction "2_2") (pintype "passive"))
      (node (ref "R38") (pin "2") (pinfunction "2_2") (pintype "passive"))
    )
    (net (code "109") (name "Net-(IC6C--IN)") (class "Default")
      (node (ref "IC6") (pin "9") (pinfunction "-IN_9") (pintype "input"))
      (node (ref "R30") (pin "2") (pinfunction "2_2") (pintype "passive"))
      (node (ref "R31") (pin "2") (pinfunction "2_2") (pintype "passive"))
      (node (ref "R32") (pin "1") (pinfunction "1_1") (pintype "passive"))
    )
    (net (code "110") (name "Net-(IC6C-OUT)") (class "Default")
      (node (ref "IC6") (pin "8") (pinfunction "OUT_8") (pintype "output"))
      (node (ref "R32") (pin "2") (pinfunction "2_2") (pintype "passive"))
      (node (ref "R33") (pin "2") (pinfunction "2_2") (pintype "passive"))
    )
    (net (code "111") (name "Net-(IC6D--IN)") (class "Default")
      (node (ref "IC6") (pin "13") (pinfunction "-IN_13") (pintype "input"))
      (node (ref "R25") (pin "2") (pinfunction "2_2") (pintype "passive"))
      (node (ref "R26") (pin "2") (pinfunction "2_2") (pintype "passive"))
      (node (ref "R27") (pin "1") (pinfunction "1_1") (pintype "passive"))
    )
    (net (code "112") (name "Net-(IC6D-OUT)") (class "Default")
      (node (ref "IC6") (pin "14") (pinfunction "OUT_14") (pintype "output"))
      (node (ref "R27") (pin "2") (pinfunction "2_2") (pintype "passive"))
      (node (ref "R28") (pin "2") (pinfunction "2_2") (pintype "passive"))
    )
    (net (code "113") (name "Net-(MOD_A-Pad2)") (class "Default")
      (node (ref "MOD_A") (pin "2") (pinfunction "2_2") (pintype "bidirectional"))
      (node (ref "R500") (pin "1") (pinfunction "1_1") (pintype "passive"))
    )
    (net (code "114") (name "Net-(MOD_B-Pad2)") (class "Default")
      (node (ref "MOD_B") (pin "2") (pinfunction "2_2") (pintype "bidirectional"))
      (node (ref "R600") (pin "1") (pinfunction "1_1") (pintype "passive"))
    )
    (net (code "115") (name "Net-(MOD_C-Pad2)") (class "Default")
      (node (ref "MOD_C") (pin "2") (pinfunction "2_2") (pintype "bidirectional"))
      (node (ref "R700") (pin "1") (pinfunction "1_1") (pintype "passive"))
    )
    (net (code "116") (name "Net-(MOD_D-Pad2)") (class "Default")
      (node (ref "MOD_D") (pin "2") (pinfunction "2_2") (pintype "bidirectional"))
      (node (ref "R800") (pin "1") (pinfunction "1_1") (pintype "passive"))
    )
    (net (code "117") (name "Net-(Q1-D)") (class "Default")
      (node (ref "JP8") (pin "1") (pinfunction "1_1") (pintype "passive"))
      (node (ref "JP8") (pin "2") (pinfunction "2_2") (pintype "passive"))
      (node (ref "Q1") (pin "3") (pinfunction "D_3") (pintype "passive"))
    )
    (net (code "118") (name "Net-(Q2-D)") (class "Default")
      (node (ref "JP8") (pin "10") (pinfunction "10_10") (pintype "passive"))
      (node (ref "JP8") (pin "9") (pinfunction "9_9") (pintype "passive"))
      (node (ref "Q2") (pin "3") (pinfunction "D_3") (pintype "passive"))
    )
    (net (code "119") (name "Net-(R26-Pad1)") (class "Default")
      (node (ref "R26") (pin "1") (pinfunction "1_1") (pintype "passive"))
      (node (ref "TUNE_D") (pin "2") (pinfunction "2_2") (pintype "bidirectional"))
    )
    (net (code "120") (name "Net-(R31-Pad1)") (class "Default")
      (node (ref "R31") (pin "1") (pinfunction "1_1") (pintype "passive"))
      (node (ref "TUNE_C") (pin "2") (pinfunction "2_2") (pintype "bidirectional"))
    )
    (net (code "121") (name "Net-(R36-Pad1)") (class "Default")
      (node (ref "R36") (pin "1") (pinfunction "1_1") (pintype "passive"))
      (node (ref "TUNE_B") (pin "2") (pinfunction "2_2") (pintype "bidirectional"))
    )
    (net (code "122") (name "Net-(R41-Pad1)") (class "Default")
      (node (ref "R41") (pin "1") (pinfunction "1_1") (pintype "passive"))
      (node (ref "TUNE_A") (pin "2") (pinfunction "2_2") (pintype "bidirectional"))
    )
    (net (code "123") (name "Net-(TUNEIN_A-3)") (class "Default")
      (node (ref "R40") (pin "1") (pinfunction "1_1") (pintype "passive"))
      (node (ref "TUNEIN_A") (pin "P$3") (pinfunction "3_P$3") (pintype "passive"))
    )
    (net (code "124") (name "Net-(TUNEIN_B-3)") (class "Default")
      (node (ref "R35") (pin "1") (pinfunction "1_1") (pintype "passive"))
      (node (ref "TUNEIN_B") (pin "P$3") (pinfunction "3_P$3") (pintype "passive"))
    )
    (net (code "125") (name "Net-(TUNEIN_C-3)") (class "Default")
      (node (ref "R30") (pin "1") (pinfunction "1_1") (pintype "passive"))
      (node (ref "TUNEIN_C") (pin "P$3") (pinfunction "3_P$3") (pintype "passive"))
    )
    (net (code "126") (name "Net-(TUNEIN_D-3)") (class "Default")
      (node (ref "R25") (pin "1") (pinfunction "1_1") (pintype "passive"))
      (node (ref "TUNEIN_D") (pin "P$3") (pinfunction "3_P$3") (pintype "passive"))
    )
    (net (code "127") (name "Net-(U1-IREF)") (class "Default")
      (node (ref "R57") (pin "2") (pinfunction "2_2") (pintype "passive"))
      (node (ref "U1") (pin "1") (pinfunction "IREF_1") (pintype "bidirectional"))
    )
    (net (code "128") (name "Net-(U1-SCKO)") (class "Default")
      (node (ref "TP2") (pin "TP") (pinfunction "TP_TP") (pintype "input"))
      (node (ref "U1") (pin "11") (pinfunction "SCKO_11") (pintype "bidirectional"))
    )
    (net (code "129") (name "Net-(U1-SDTO)") (class "Default")
      (node (ref "TP1") (pin "TP") (pinfunction "TP_TP") (pintype "input"))
      (node (ref "U1") (pin "12") (pinfunction "SDTO_12") (pintype "bidirectional"))
    )
    (net (code "130") (name "unconnected-(ANG2-Pad6)") (class "Default")
      (node (ref "ANG2") (pin "6") (pinfunction "6_6") (pintype "passive"))
    )
    (net (code "131") (name "unconnected-(ENV_A-5-PadP$1)") (class "Default")
      (node (ref "ENV_A") (pin "P$1") (pinfunction "5_P$1") (pintype "passive"))
    )
    (net (code "132") (name "unconnected-(ENV_B-5-PadP$1)") (class "Default")
      (node (ref "ENV_B") (pin "P$1") (pinfunction "5_P$1") (pintype "passive"))
    )
    (net (code "133") (name "unconnected-(ENV_C-5-PadP$1)") (class "Default")
      (node (ref "ENV_C") (pin "P$1") (pinfunction "5_P$1") (pintype "passive"))
    )
    (net (code "134") (name "unconnected-(ENV_D-5-PadP$1)") (class "Default")
      (node (ref "ENV_D") (pin "P$1") (pinfunction "5_P$1") (pintype "passive"))
    )
    (net (code "135") (name "unconnected-(OUT_L-4-PadP$2)") (class "Default")
      (node (ref "OUT_L") (pin "P$2") (pinfunction "4_P$2") (pintype "passive"))
    )
    (net (code "136") (name "unconnected-(OUT_R-4-PadP$2)") (class "Default")
      (node (ref "OUT_R") (pin "P$2") (pinfunction "4_P$2") (pintype "passive"))
    )
    (net (code "137") (name "unconnected-(USB_D-Pad1)") (class "Default")
      (node (ref "USB_D") (pin "1") (pinfunction "1_1") (pintype "passive"))
    )
    (net (code "138") (name "unconnected-(USB_D-Pad2)") (class "Default")
      (node (ref "USB_D") (pin "2") (pinfunction "2_2") (pintype "passive"))
    )
    (net (code "139") (name "unconnected-(USB_D-Pad3)") (class "Default")
      (node (ref "USB_D") (pin "3") (pinfunction "3_3") (pintype "passive"))
    )
    (net (code "140") (name "unconnected-(USB_D-Pad4)") (class "Default")
      (node (ref "USB_D") (pin "4") (pinfunction "4_4") (pintype "passive"))
    )
    (net (code "141") (name "unconnected-(X3-S1-PadM1)") (class "Default")
      (node (ref "X3") (pin "M1") (pinfunction "S1_M1") (pintype "passive"))
    )
    (net (code "142") (name "unconnected-(X3-S2-PadM2)") (class "Default")
      (node (ref "X3") (pin "M2") (pinfunction "S2_M2") (pintype "passive"))
    )
  )
)
